# marbles_v70.net
KiCad netlist of a schematic drawn in EAGLE
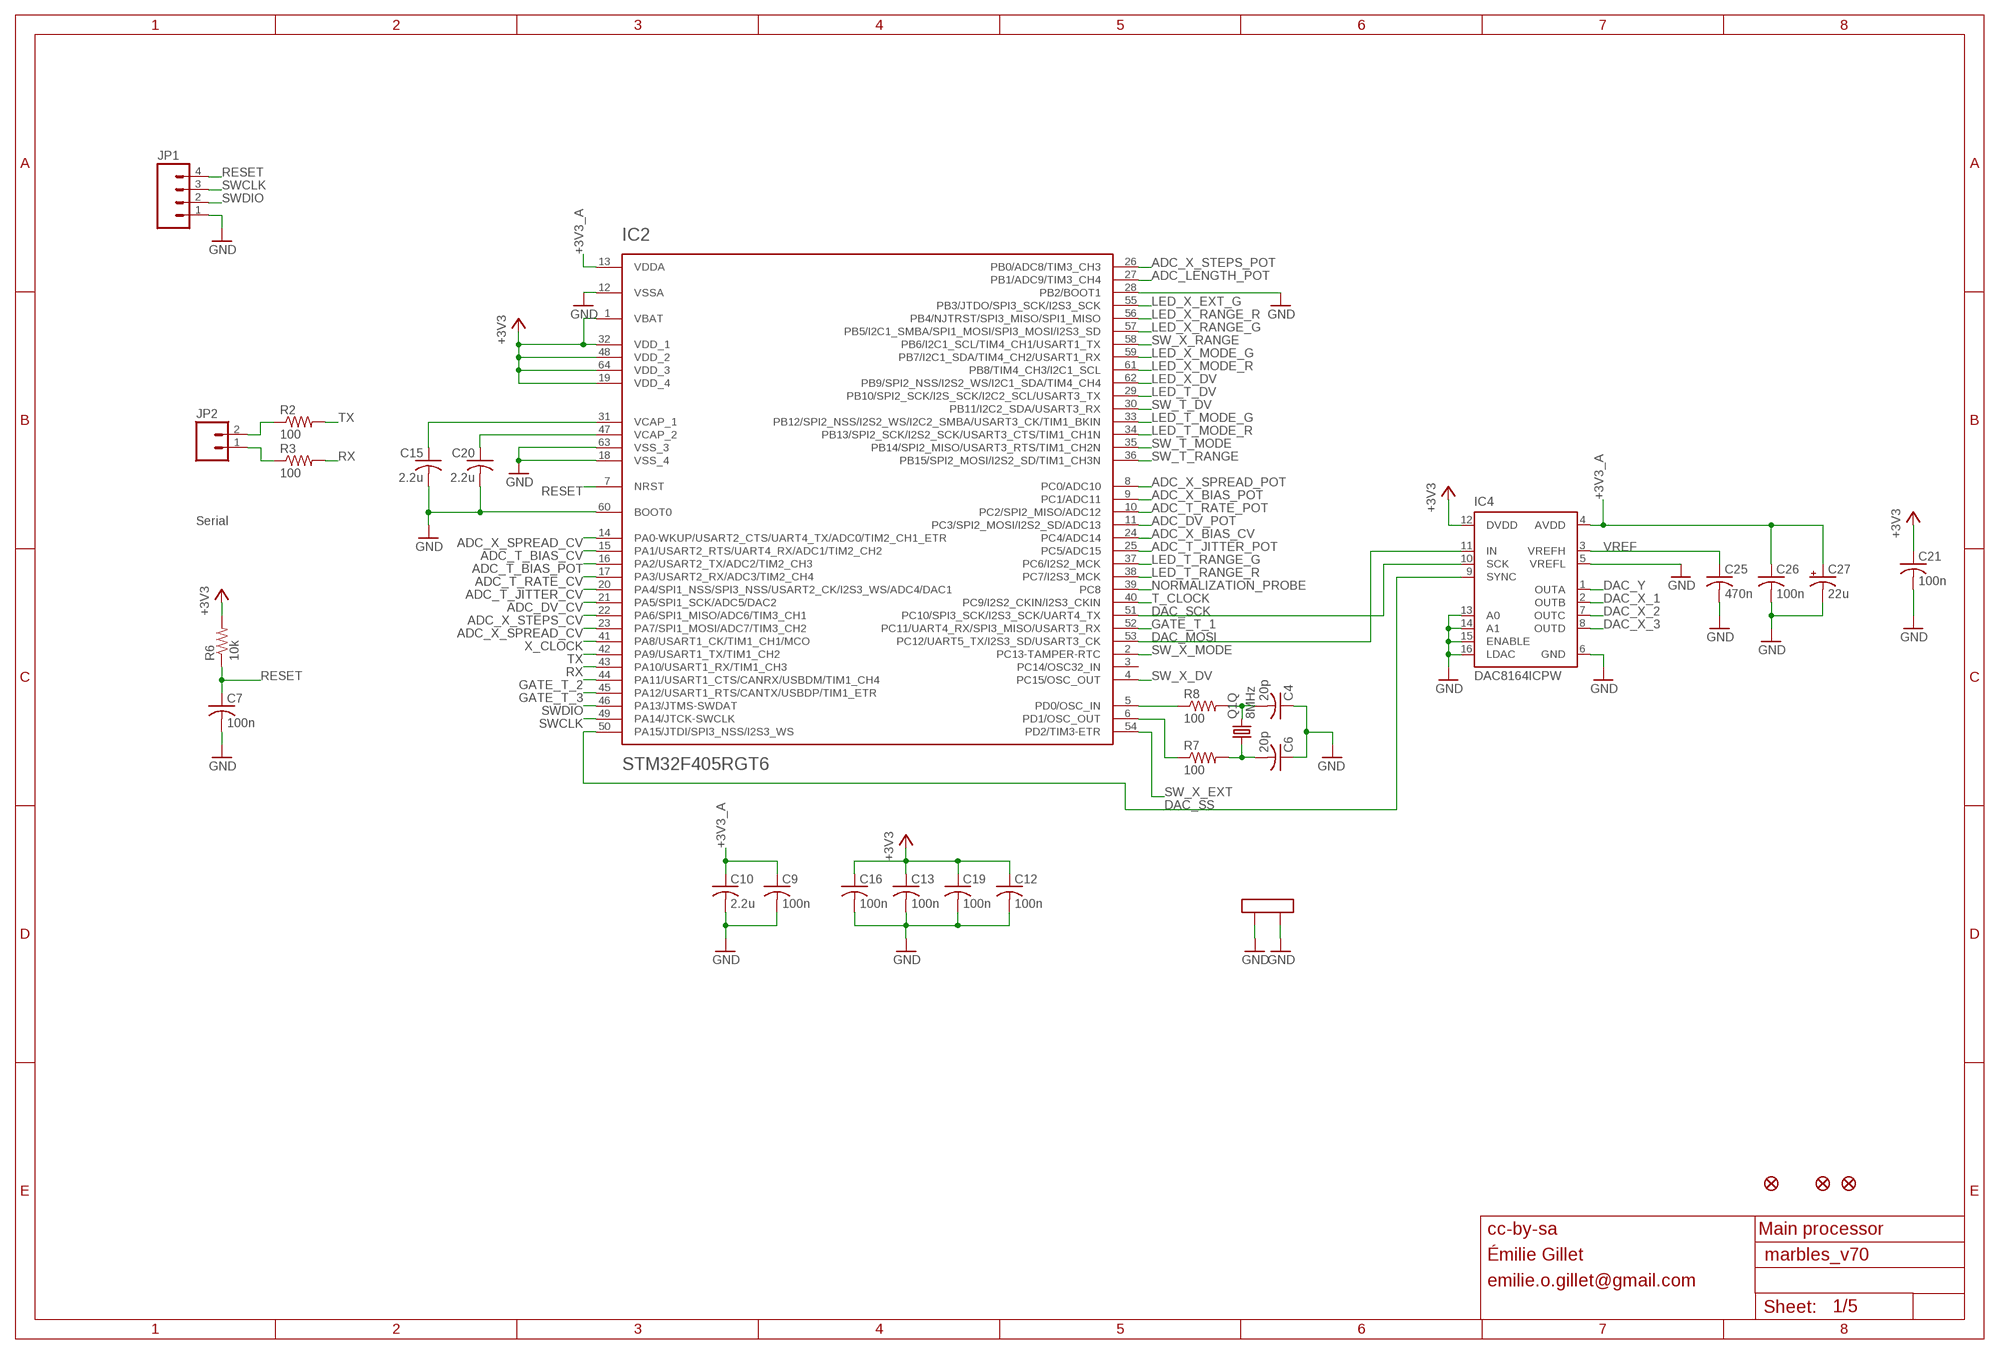
[diagram p0: schematic, sheet 1]
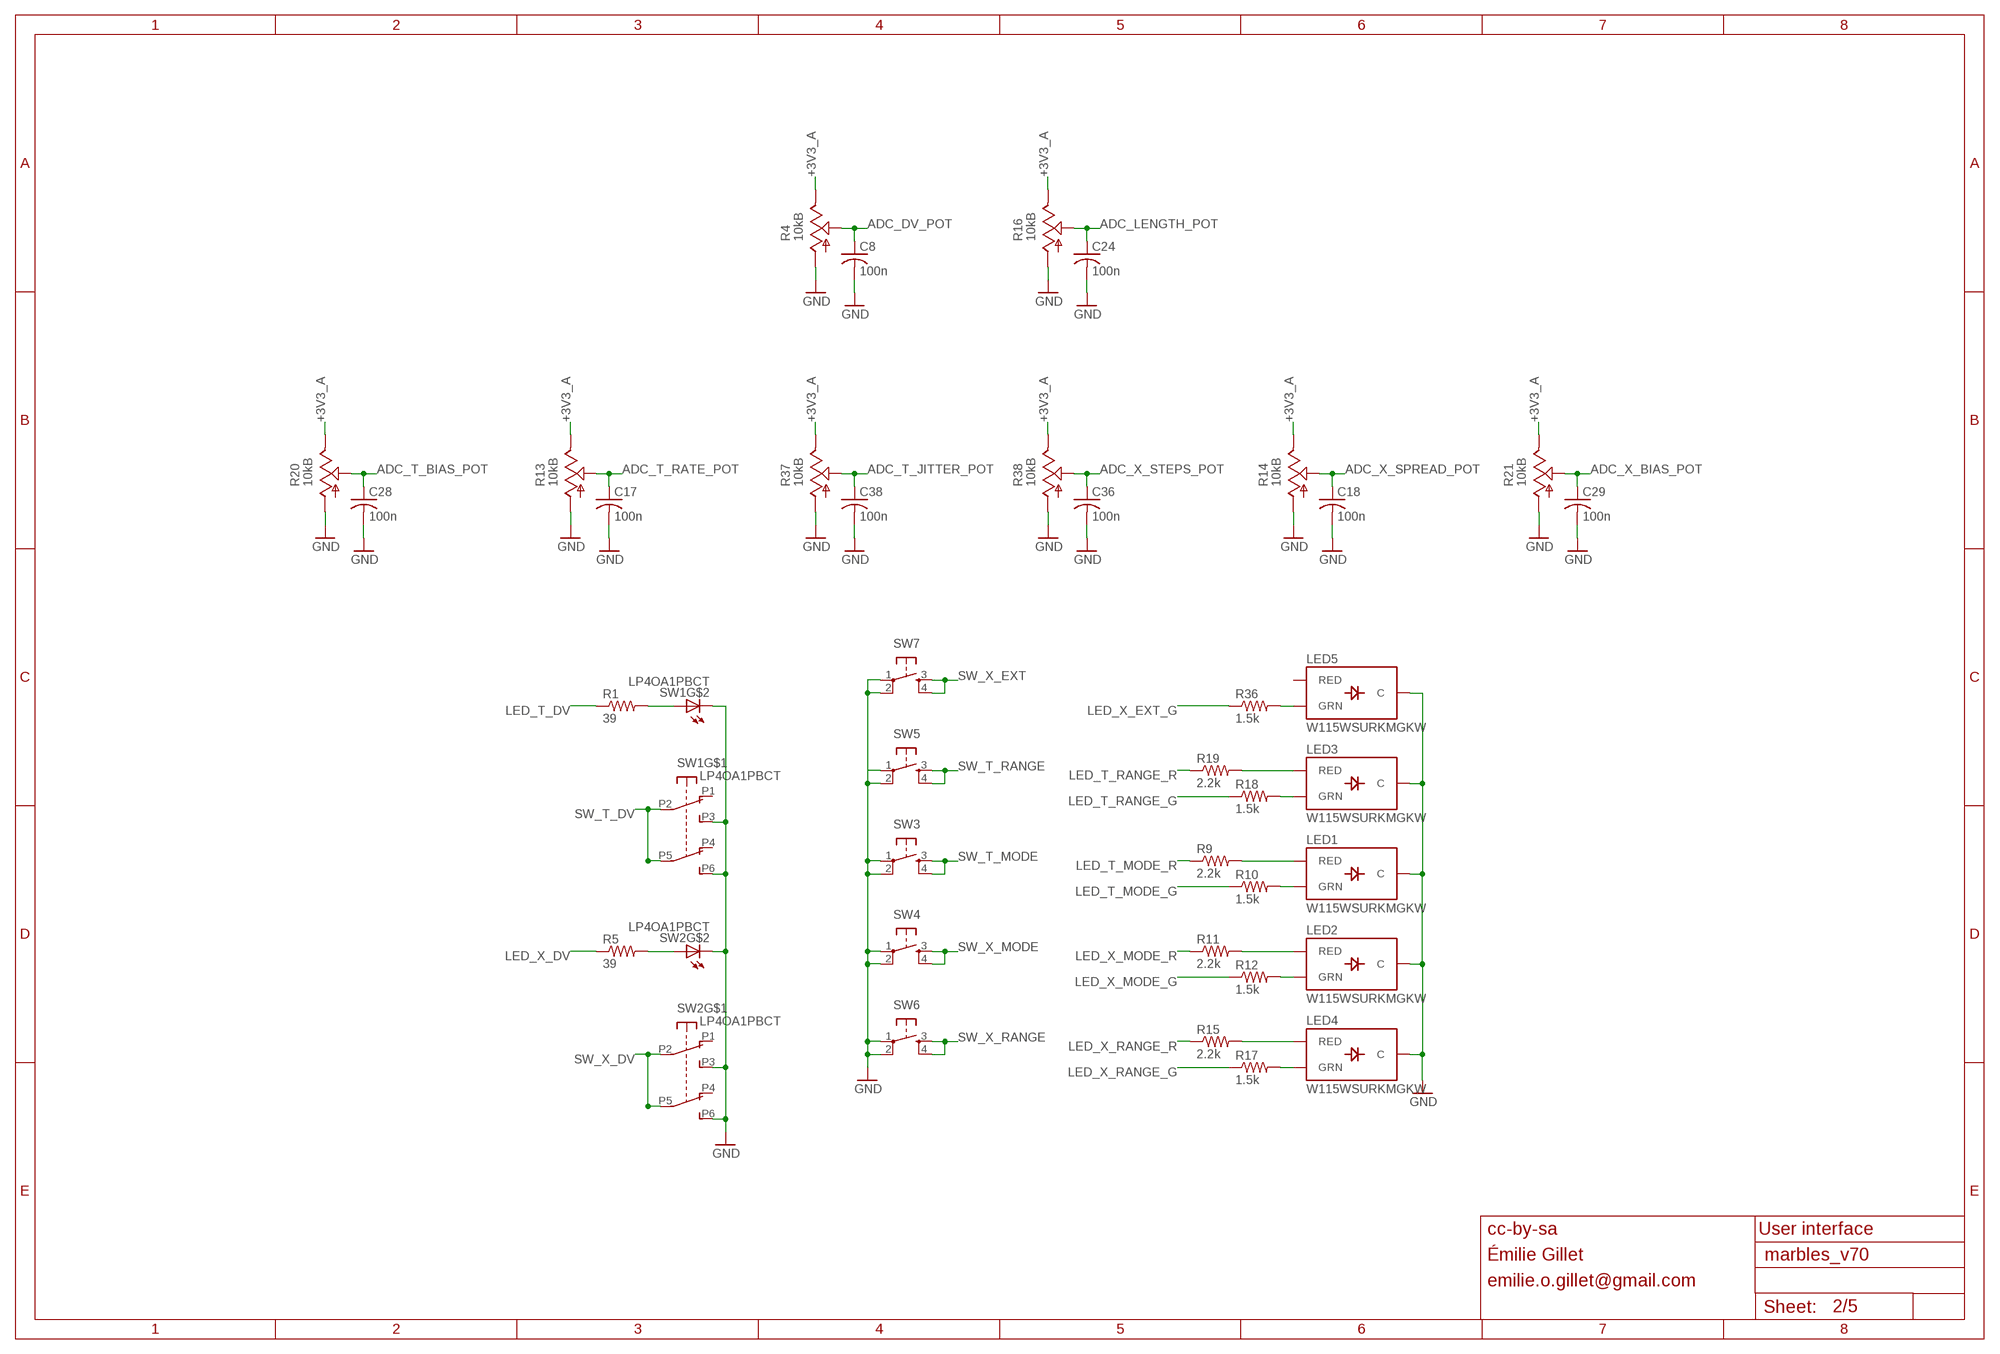
[diagram p1: schematic, sheet 2]
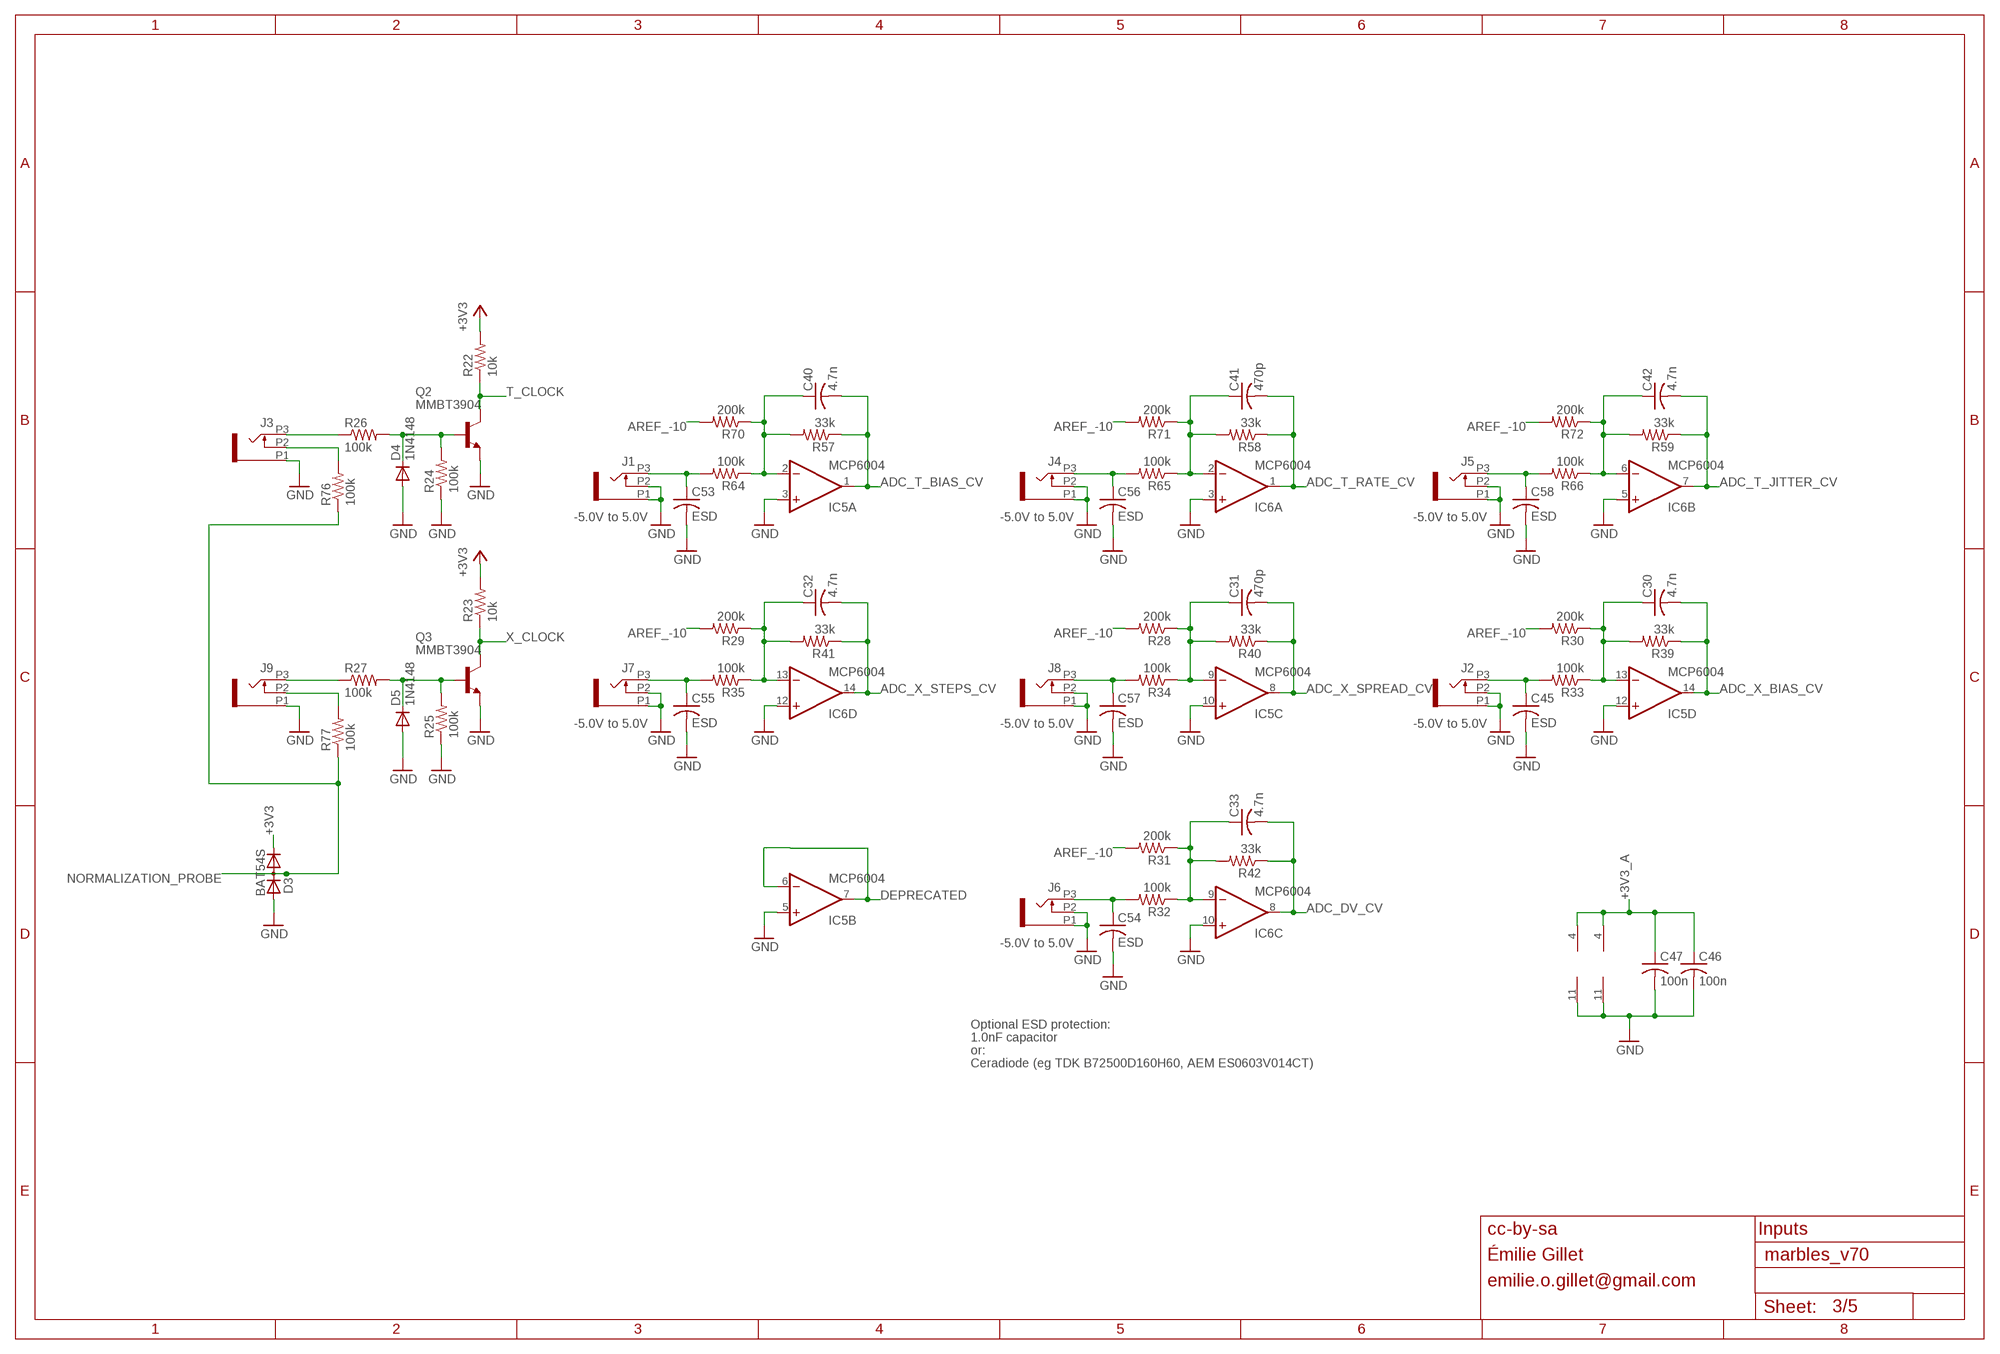
[diagram p2: schematic, sheet 3]
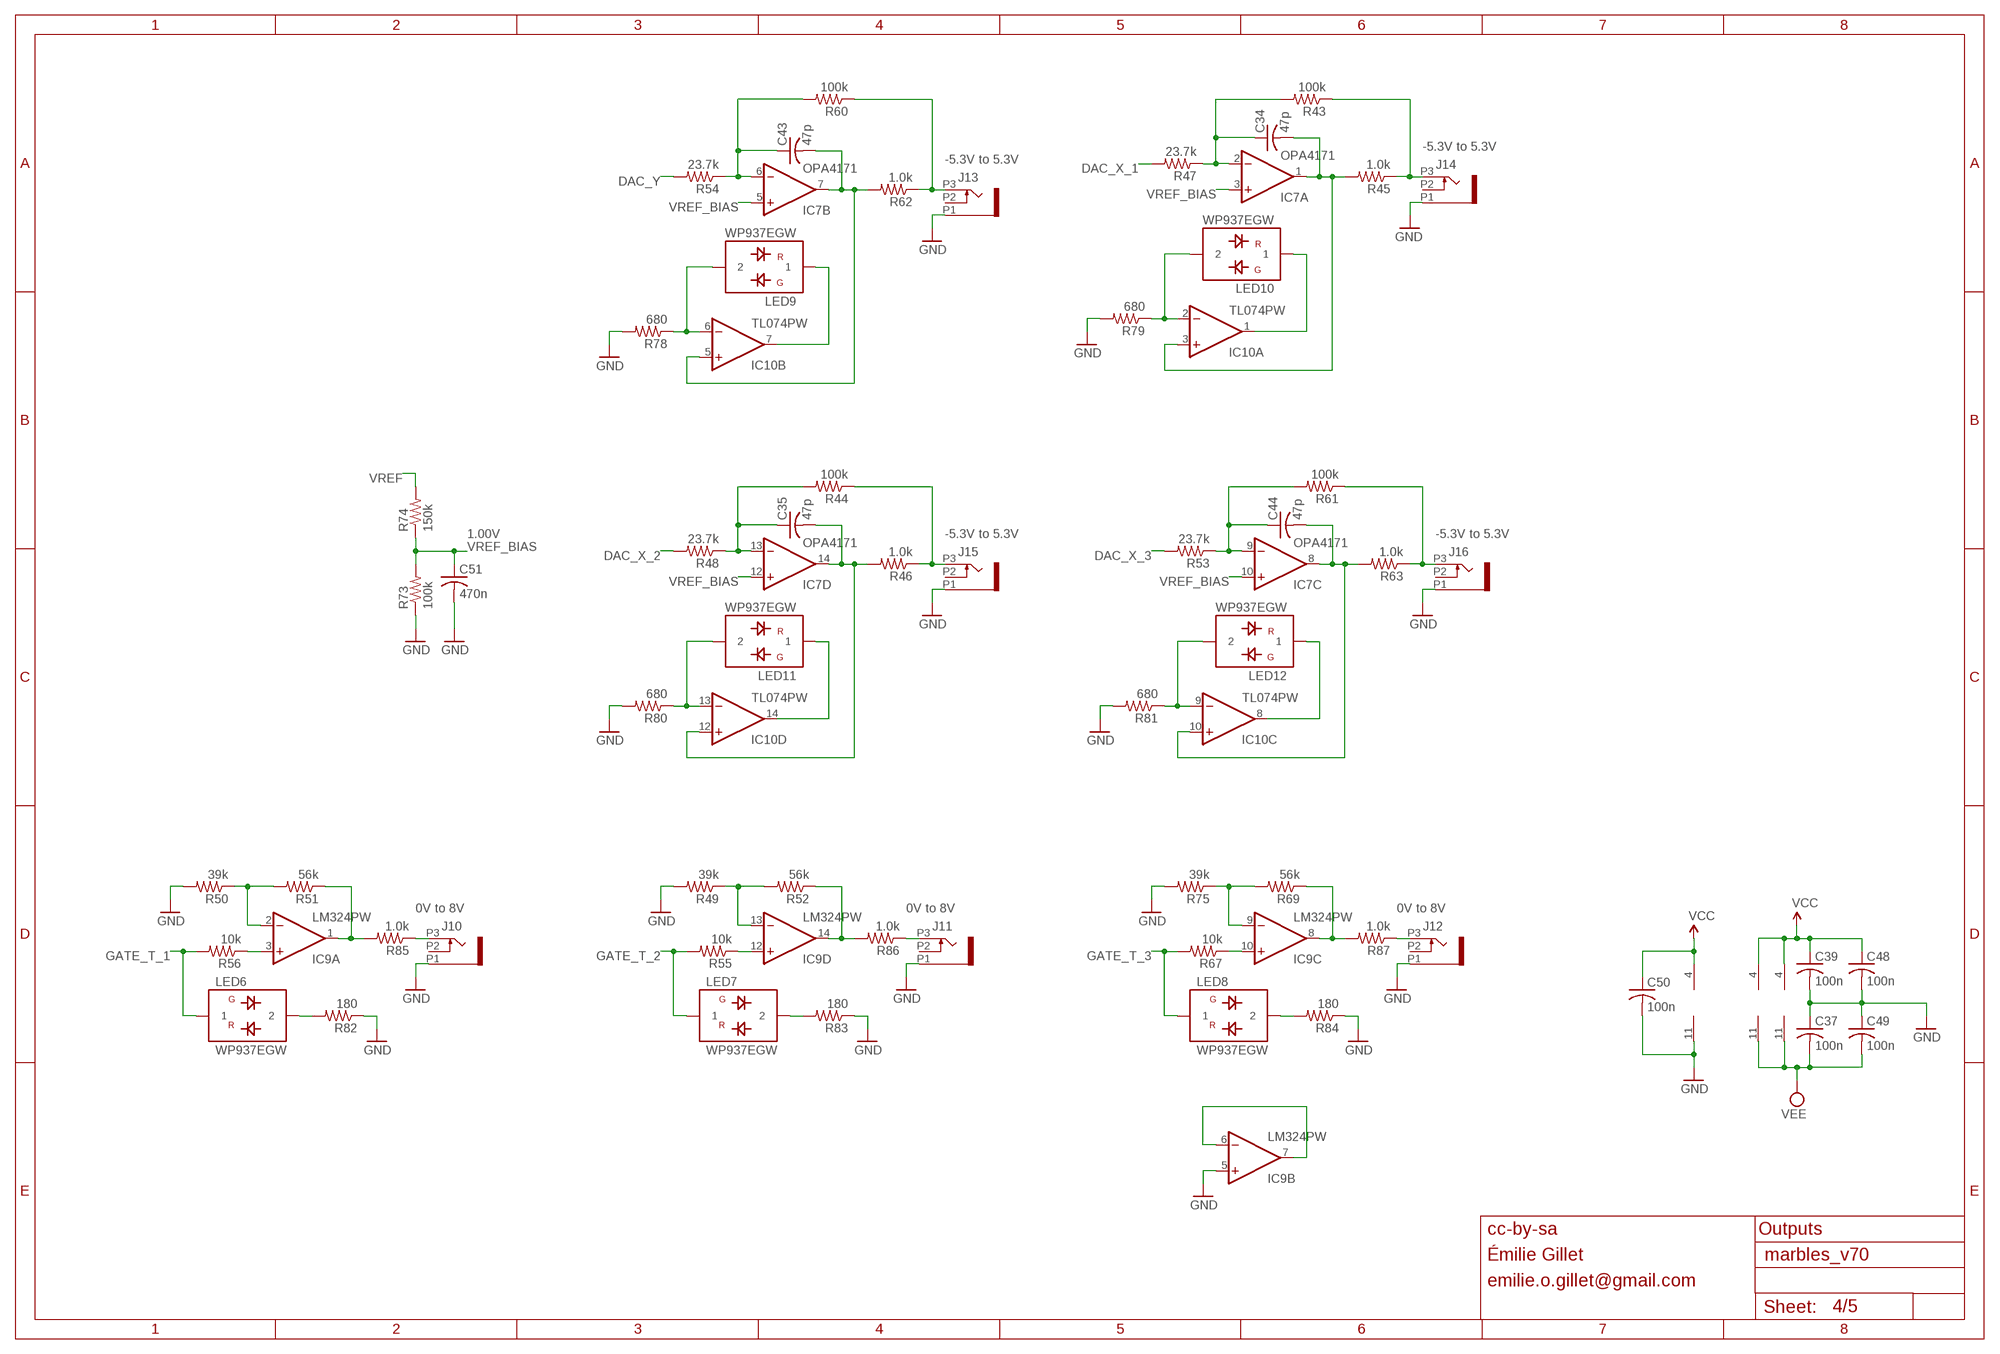
[diagram p3: schematic, sheet 4]
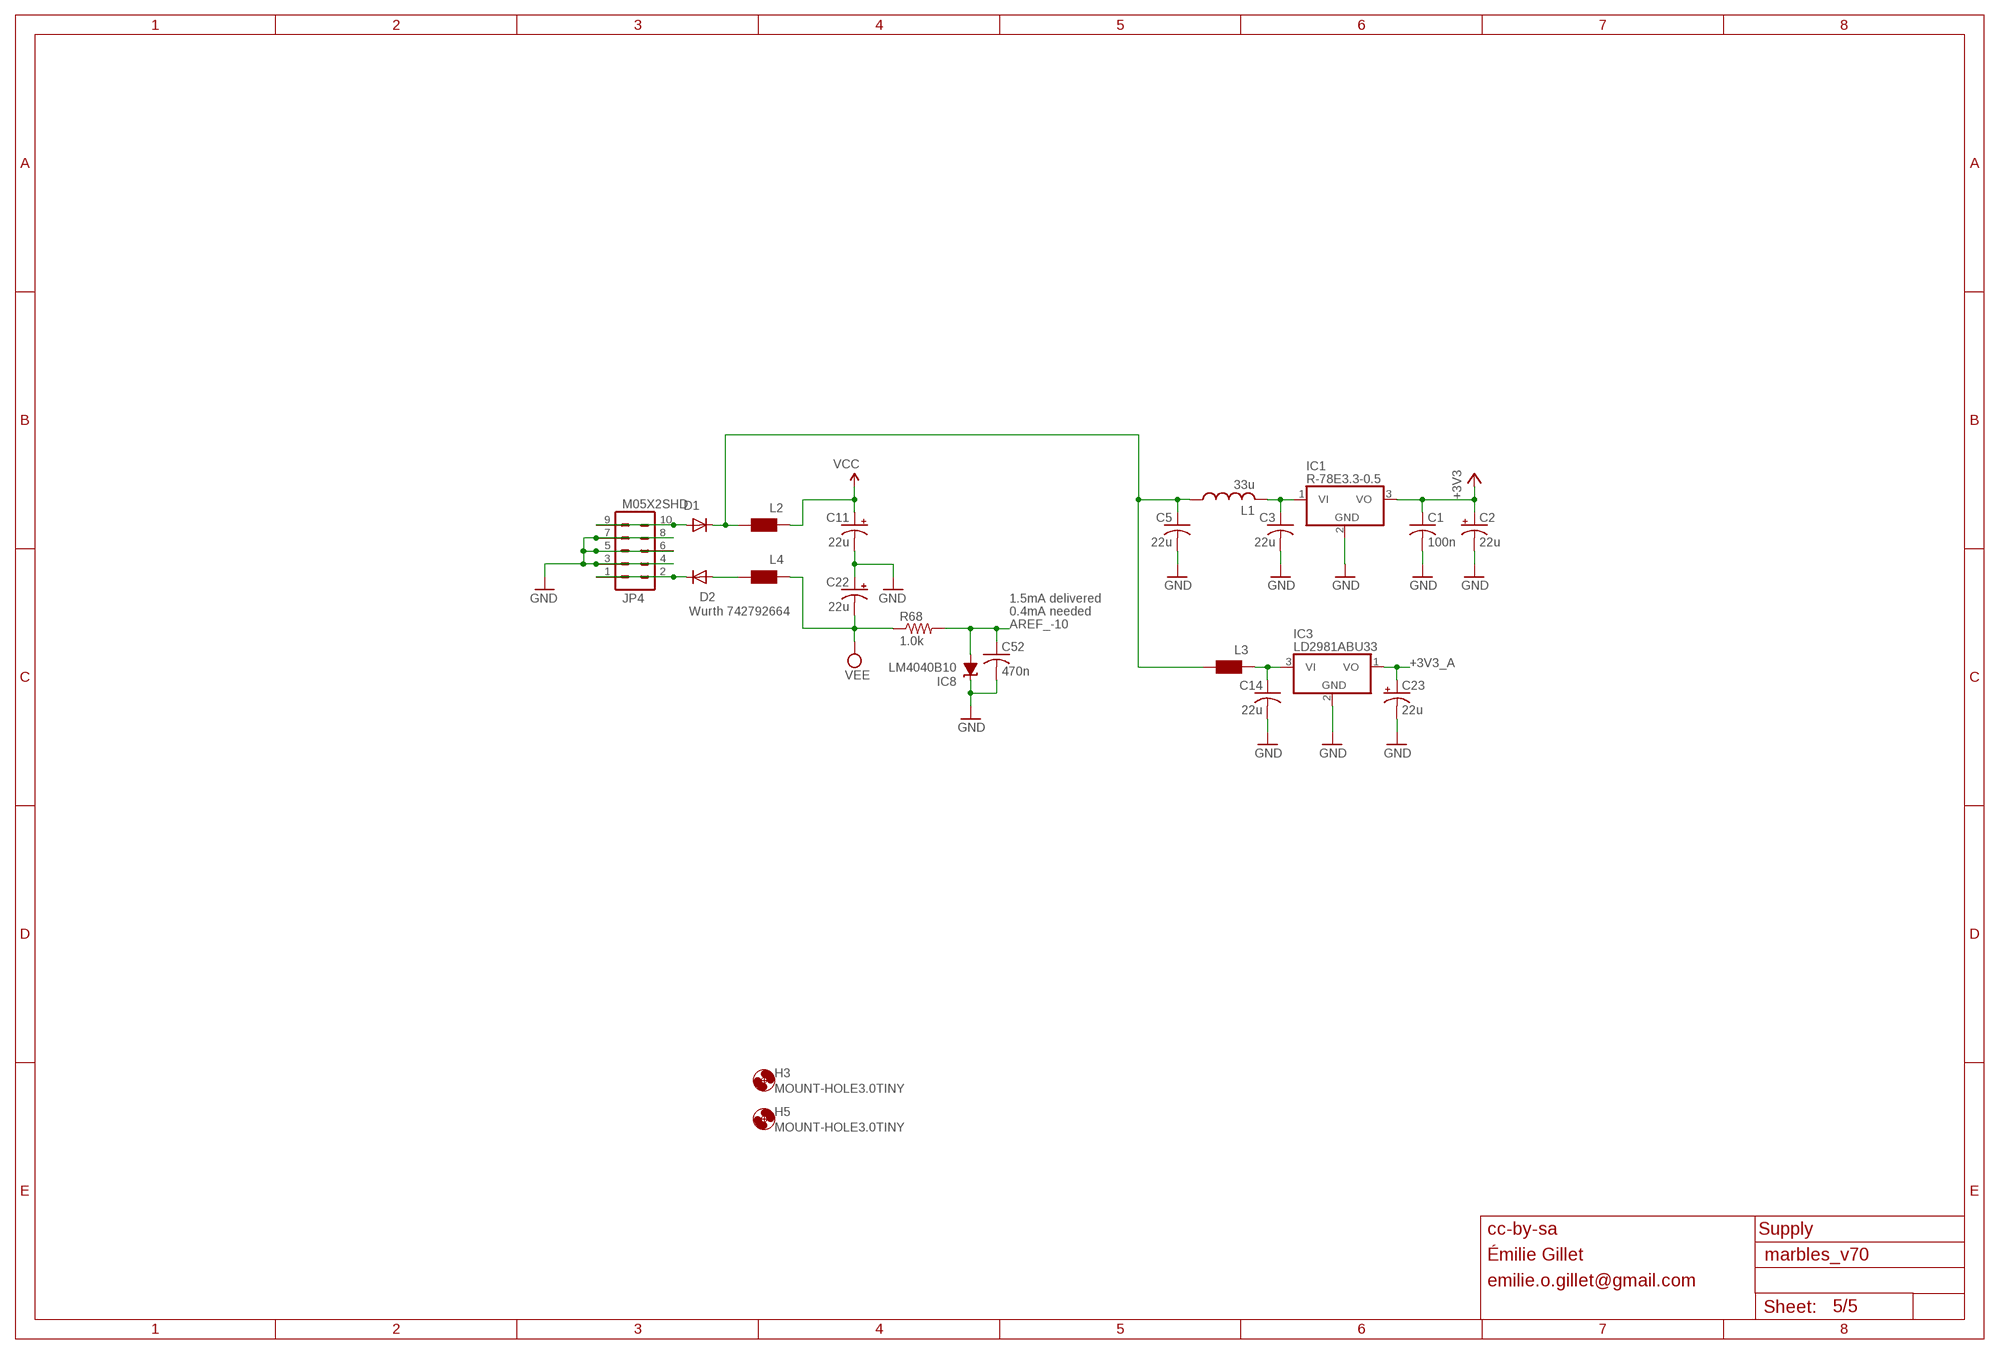
[diagram p4: schematic, sheet 5]

(export (version "E")
  (design (tool "Eeschema 10.0.6"))
  (components
    (comp (ref "C34")
      (value "47p")
      (footprint "eagle-import:C0402")
      (libsource (lib "eagle-import") (part "C-USC0402"))
    )
    (comp (ref "C35")
      (value "47p")
      (footprint "eagle-import:C0402")
      (libsource (lib "eagle-import") (part "C-USC0402"))
    )
    (comp (ref "C37")
      (value "100n")
      (footprint "eagle-import:C0402")
      (libsource (lib "eagle-import") (part "C-USC0402"))
    )
    (comp (ref "C39")
      (value "100n")
      (footprint "eagle-import:C0402")
      (libsource (lib "eagle-import") (part "C-USC0402"))
    )
    (comp (ref "C43")
      (value "47p")
      (footprint "eagle-import:C0402")
      (libsource (lib "eagle-import") (part "C-USC0402"))
    )
    (comp (ref "C44")
      (value "47p")
      (footprint "eagle-import:C0402")
      (libsource (lib "eagle-import") (part "C-USC0402"))
    )
    (comp (ref "C48")
      (value "100n")
      (footprint "eagle-import:C0402")
      (libsource (lib "eagle-import") (part "C-USC0402"))
    )
    (comp (ref "C49")
      (value "100n")
      (footprint "eagle-import:C0402")
      (libsource (lib "eagle-import") (part "C-USC0402"))
    )
    (comp (ref "C50")
      (value "100n")
      (footprint "eagle-import:C0402")
      (libsource (lib "eagle-import") (part "C-USC0402"))
    )
    (comp (ref "C51")
      (value "470n")
      (footprint "eagle-import:C0402")
      (libsource (lib "eagle-import") (part "C-USC0402"))
    )
    (comp (ref "IC7")
      (value "OPA4171")
      (footprint "eagle-import:TSSOP14_065")
      (libsource (lib "eagle-import") (part "TL074PW"))
    )
    (comp (ref "IC9")
      (value "LM324PW")
      (footprint "eagle-import:TSSOP14_065")
      (libsource (lib "eagle-import") (part "TL074PW"))
    )
    (comp (ref "IC10")
      (value "TL074PW")
      (footprint "eagle-import:TSSOP14_065")
      (libsource (lib "eagle-import") (part "TL074PW"))
    )
    (comp (ref "J10")
      (value "PJ301_THONKICONN6")
      (footprint "eagle-import:WQP_PJ_301M6")
      (libsource (lib "eagle-import") (part "PJ301_THONKICONN6"))
    )
    (comp (ref "J11")
      (value "PJ301_THONKICONN6")
      (footprint "eagle-import:WQP_PJ_301M6")
      (libsource (lib "eagle-import") (part "PJ301_THONKICONN6"))
    )
    (comp (ref "J12")
      (value "PJ301_THONKICONN6")
      (footprint "eagle-import:WQP_PJ_301M6")
      (libsource (lib "eagle-import") (part "PJ301_THONKICONN6"))
    )
    (comp (ref "J13")
      (value "PJ301_THONKICONN6")
      (footprint "eagle-import:WQP_PJ_301M6")
      (libsource (lib "eagle-import") (part "PJ301_THONKICONN6"))
    )
    (comp (ref "J14")
      (value "PJ301_THONKICONN6")
      (footprint "eagle-import:WQP_PJ_301M6")
      (libsource (lib "eagle-import") (part "PJ301_THONKICONN6"))
    )
    (comp (ref "J15")
      (value "PJ301_THONKICONN6")
      (footprint "eagle-import:WQP_PJ_301M6")
      (libsource (lib "eagle-import") (part "PJ301_THONKICONN6"))
    )
    (comp (ref "J16")
      (value "PJ301_THONKICONN6")
      (footprint "eagle-import:WQP_PJ_301M6")
      (libsource (lib "eagle-import") (part "PJ301_THONKICONN6"))
    )
    (comp (ref "LED6")
      (value "WP937EGW")
      (footprint "eagle-import:LED3MM")
      (libsource (lib "eagle-import") (part "LED-BICOLOR-SHARED-THROUGHHOLE"))
    )
    (comp (ref "LED7")
      (value "WP937EGW")
      (footprint "eagle-import:LED3MM")
      (libsource (lib "eagle-import") (part "LED-BICOLOR-SHARED-THROUGHHOLE"))
    )
    (comp (ref "LED8")
      (value "WP937EGW")
      (footprint "eagle-import:LED3MM")
      (libsource (lib "eagle-import") (part "LED-BICOLOR-SHARED-THROUGHHOLE"))
    )
    (comp (ref "LED9")
      (value "WP937EGW")
      (footprint "eagle-import:LED3MM")
      (libsource (lib "eagle-import") (part "LED-BICOLOR-SHARED-THROUGHHOLE"))
    )
    (comp (ref "LED10")
      (value "WP937EGW")
      (footprint "eagle-import:LED3MM")
      (libsource (lib "eagle-import") (part "LED-BICOLOR-SHARED-THROUGHHOLE"))
    )
    (comp (ref "LED11")
      (value "WP937EGW")
      (footprint "eagle-import:LED3MM")
      (libsource (lib "eagle-import") (part "LED-BICOLOR-SHARED-THROUGHHOLE"))
    )
    (comp (ref "LED12")
      (value "WP937EGW")
      (footprint "eagle-import:LED3MM")
      (libsource (lib "eagle-import") (part "LED-BICOLOR-SHARED-THROUGHHOLE"))
    )
    (comp (ref "R43")
      (value "100k")
      (footprint "eagle-import:R0402")
      (libsource (lib "eagle-import") (part "R-US_R0402"))
    )
    (comp (ref "R44")
      (value "100k")
      (footprint "eagle-import:R0402")
      (libsource (lib "eagle-import") (part "R-US_R0402"))
    )
    (comp (ref "R45")
      (value "1.0k")
      (footprint "eagle-import:R0603")
      (libsource (lib "eagle-import") (part "R-US_R0603"))
    )
    (comp (ref "R46")
      (value "1.0k")
      (footprint "eagle-import:R0603")
      (libsource (lib "eagle-import") (part "R-US_R0603"))
    )
    (comp (ref "R47")
      (value "23.7k")
      (footprint "eagle-import:R0402")
      (libsource (lib "eagle-import") (part "R-US_R0402"))
    )
    (comp (ref "R48")
      (value "23.7k")
      (footprint "eagle-import:R0402")
      (libsource (lib "eagle-import") (part "R-US_R0402"))
    )
    (comp (ref "R49")
      (value "39k")
      (footprint "eagle-import:R0402")
      (libsource (lib "eagle-import") (part "R-US_R0402"))
    )
    (comp (ref "R50")
      (value "39k")
      (footprint "eagle-import:R0402")
      (libsource (lib "eagle-import") (part "R-US_R0402"))
    )
    (comp (ref "R51")
      (value "56k")
      (footprint "eagle-import:R0402")
      (libsource (lib "eagle-import") (part "R-US_R0402"))
    )
    (comp (ref "R52")
      (value "56k")
      (footprint "eagle-import:R0402")
      (libsource (lib "eagle-import") (part "R-US_R0402"))
    )
    (comp (ref "R53")
      (value "23.7k")
      (footprint "eagle-import:R0402")
      (libsource (lib "eagle-import") (part "R-US_R0402"))
    )
    (comp (ref "R54")
      (value "23.7k")
      (footprint "eagle-import:R0402")
      (libsource (lib "eagle-import") (part "R-US_R0402"))
    )
    (comp (ref "R55")
      (value "10k")
      (footprint "eagle-import:R0402")
      (libsource (lib "eagle-import") (part "R-US_R0402"))
    )
    (comp (ref "R56")
      (value "10k")
      (footprint "eagle-import:R0402")
      (libsource (lib "eagle-import") (part "R-US_R0402"))
    )
    (comp (ref "R60")
      (value "100k")
      (footprint "eagle-import:R0402")
      (libsource (lib "eagle-import") (part "R-US_R0402"))
    )
    (comp (ref "R61")
      (value "100k")
      (footprint "eagle-import:R0402")
      (libsource (lib "eagle-import") (part "R-US_R0402"))
    )
    (comp (ref "R62")
      (value "1.0k")
      (footprint "eagle-import:R0603")
      (libsource (lib "eagle-import") (part "R-US_R0603"))
    )
    (comp (ref "R63")
      (value "1.0k")
      (footprint "eagle-import:R0603")
      (libsource (lib "eagle-import") (part "R-US_R0603"))
    )
    (comp (ref "R67")
      (value "10k")
      (footprint "eagle-import:R0402")
      (libsource (lib "eagle-import") (part "R-US_R0402"))
    )
    (comp (ref "R69")
      (value "56k")
      (footprint "eagle-import:R0402")
      (libsource (lib "eagle-import") (part "R-US_R0402"))
    )
    (comp (ref "R73")
      (value "100k")
      (footprint "eagle-import:R0402")
      (libsource (lib "eagle-import") (part "R-US_R0402"))
    )
    (comp (ref "R74")
      (value "150k")
      (footprint "eagle-import:R0402")
      (libsource (lib "eagle-import") (part "R-US_R0402"))
    )
    (comp (ref "R75")
      (value "39k")
      (footprint "eagle-import:R0402")
      (libsource (lib "eagle-import") (part "R-US_R0402"))
    )
    (comp (ref "R78")
      (value "680")
      (footprint "eagle-import:R0402")
      (libsource (lib "eagle-import") (part "R-US_R0402"))
    )
    (comp (ref "R79")
      (value "680")
      (footprint "eagle-import:R0402")
      (libsource (lib "eagle-import") (part "R-US_R0402"))
    )
    (comp (ref "R80")
      (value "680")
      (footprint "eagle-import:R0402")
      (libsource (lib "eagle-import") (part "R-US_R0402"))
    )
    (comp (ref "R81")
      (value "680")
      (footprint "eagle-import:R0402")
      (libsource (lib "eagle-import") (part "R-US_R0402"))
    )
    (comp (ref "R82")
      (value "180")
      (footprint "eagle-import:R0402")
      (libsource (lib "eagle-import") (part "R-US_R0402"))
    )
    (comp (ref "R83")
      (value "180")
      (footprint "eagle-import:R0402")
      (libsource (lib "eagle-import") (part "R-US_R0402"))
    )
    (comp (ref "R84")
      (value "180")
      (footprint "eagle-import:R0402")
      (libsource (lib "eagle-import") (part "R-US_R0402"))
    )
    (comp (ref "R85")
      (value "1.0k")
      (footprint "eagle-import:R0603")
      (libsource (lib "eagle-import") (part "R-US_R0603"))
    )
    (comp (ref "R86")
      (value "1.0k")
      (footprint "eagle-import:R0603")
      (libsource (lib "eagle-import") (part "R-US_R0603"))
    )
    (comp (ref "R87")
      (value "1.0k")
      (footprint "eagle-import:R0603")
      (libsource (lib "eagle-import") (part "R-US_R0603"))
    )
    (comp (ref "C8")
      (value "100n")
      (footprint "eagle-import:C0402")
      (libsource (lib "eagle-import") (part "C-USC0402"))
    )
    (comp (ref "C17")
      (value "100n")
      (footprint "eagle-import:C0402")
      (libsource (lib "eagle-import") (part "C-USC0402"))
    )
    (comp (ref "C18")
      (value "100n")
      (footprint "eagle-import:C0402")
      (libsource (lib "eagle-import") (part "C-USC0402"))
    )
    (comp (ref "C24")
      (value "100n")
      (footprint "eagle-import:C0402")
      (libsource (lib "eagle-import") (part "C-USC0402"))
    )
    (comp (ref "C28")
      (value "100n")
      (footprint "eagle-import:C0402")
      (libsource (lib "eagle-import") (part "C-USC0402"))
    )
    (comp (ref "C29")
      (value "100n")
      (footprint "eagle-import:C0402")
      (libsource (lib "eagle-import") (part "C-USC0402"))
    )
    (comp (ref "C36")
      (value "100n")
      (footprint "eagle-import:C0402")
      (libsource (lib "eagle-import") (part "C-USC0402"))
    )
    (comp (ref "C38")
      (value "100n")
      (footprint "eagle-import:C0402")
      (libsource (lib "eagle-import") (part "C-USC0402"))
    )
    (comp (ref "LED1")
      (value "W115WSURKMGKW")
      (footprint "eagle-import:LED-BICOLOR-THROUGHHOLE-2.54")
      (libsource (lib "eagle-import") (part "LED-BICOLOR-THROUGHHOLE2.54"))
    )
    (comp (ref "LED2")
      (value "W115WSURKMGKW")
      (footprint "eagle-import:LED-BICOLOR-THROUGHHOLE-2.54")
      (libsource (lib "eagle-import") (part "LED-BICOLOR-THROUGHHOLE2.54"))
    )
    (comp (ref "LED3")
      (value "W115WSURKMGKW")
      (footprint "eagle-import:LED-BICOLOR-THROUGHHOLE-2.54")
      (libsource (lib "eagle-import") (part "LED-BICOLOR-THROUGHHOLE2.54"))
    )
    (comp (ref "LED4")
      (value "W115WSURKMGKW")
      (footprint "eagle-import:LED-BICOLOR-THROUGHHOLE-2.54")
      (libsource (lib "eagle-import") (part "LED-BICOLOR-THROUGHHOLE2.54"))
    )
    (comp (ref "LED5")
      (value "W115WSURKMGKW")
      (footprint "eagle-import:LED-BICOLOR-THROUGHHOLE-2.54")
      (libsource (lib "eagle-import") (part "LED-BICOLOR-THROUGHHOLE2.54"))
    )
    (comp (ref "R1")
      (value "39")
      (footprint "eagle-import:R0402")
      (libsource (lib "eagle-import") (part "R-US_R0402"))
    )
    (comp (ref "R4")
      (value "10kB")
      (footprint "eagle-import:ALPS_POT_VERTICAL_PS")
      (libsource (lib "eagle-import") (part "POT_USVERTICAL_PS"))
    )
    (comp (ref "R5")
      (value "39")
      (footprint "eagle-import:R0402")
      (libsource (lib "eagle-import") (part "R-US_R0402"))
    )
    (comp (ref "R9")
      (value "2.2k")
      (footprint "eagle-import:R0402")
      (libsource (lib "eagle-import") (part "R-US_R0402"))
    )
    (comp (ref "R10")
      (value "1.5k")
      (footprint "eagle-import:R0402")
      (libsource (lib "eagle-import") (part "R-US_R0402"))
    )
    (comp (ref "R11")
      (value "2.2k")
      (footprint "eagle-import:R0402")
      (libsource (lib "eagle-import") (part "R-US_R0402"))
    )
    (comp (ref "R12")
      (value "1.5k")
      (footprint "eagle-import:R0402")
      (libsource (lib "eagle-import") (part "R-US_R0402"))
    )
    (comp (ref "R13")
      (value "10kB")
      (footprint "eagle-import:ALPS_POT_VERTICAL_PS")
      (libsource (lib "eagle-import") (part "POT_USVERTICAL_PS"))
    )
    (comp (ref "R14")
      (value "10kB")
      (footprint "eagle-import:ALPS_POT_VERTICAL_PS")
      (libsource (lib "eagle-import") (part "POT_USVERTICAL_PS"))
    )
    (comp (ref "R15")
      (value "2.2k")
      (footprint "eagle-import:R0402")
      (libsource (lib "eagle-import") (part "R-US_R0402"))
    )
    (comp (ref "R16")
      (value "10kB")
      (footprint "eagle-import:ALPS_POT_VERTICAL_PS")
      (libsource (lib "eagle-import") (part "POT_USVERTICAL_PS"))
    )
    (comp (ref "R17")
      (value "1.5k")
      (footprint "eagle-import:R0402")
      (libsource (lib "eagle-import") (part "R-US_R0402"))
    )
    (comp (ref "R18")
      (value "1.5k")
      (footprint "eagle-import:R0402")
      (libsource (lib "eagle-import") (part "R-US_R0402"))
    )
    (comp (ref "R19")
      (value "2.2k")
      (footprint "eagle-import:R0402")
      (libsource (lib "eagle-import") (part "R-US_R0402"))
    )
    (comp (ref "R20")
      (value "10kB")
      (footprint "eagle-import:ALPS_POT_VERTICAL_PS")
      (libsource (lib "eagle-import") (part "POT_USVERTICAL_PS"))
    )
    (comp (ref "R21")
      (value "10kB")
      (footprint "eagle-import:ALPS_POT_VERTICAL_PS")
      (libsource (lib "eagle-import") (part "POT_USVERTICAL_PS"))
    )
    (comp (ref "R36")
      (value "1.5k")
      (footprint "eagle-import:R0402")
      (libsource (lib "eagle-import") (part "R-US_R0402"))
    )
    (comp (ref "R37")
      (value "10kB")
      (footprint "eagle-import:ALPS_POT_VERTICAL_PS")
      (libsource (lib "eagle-import") (part "POT_USVERTICAL_PS"))
    )
    (comp (ref "R38")
      (value "10kB")
      (footprint "eagle-import:ALPS_POT_VERTICAL_PS")
      (libsource (lib "eagle-import") (part "POT_USVERTICAL_PS"))
    )
    (comp (ref "SW1")
      (value "LP4OA1PBCT")
      (footprint "eagle-import:LP4OA1PBCT")
      (libsource (lib "eagle-import") (part "LP4OA1PBCT"))
    )
    (comp (ref "SW2")
      (value "LP4OA1PBCT")
      (footprint "eagle-import:LP4OA1PBCT")
      (libsource (lib "eagle-import") (part "LP4OA1PBCT"))
    )
    (comp (ref "SW3")
      (value "TAC_SWITCHPTH")
      (footprint "eagle-import:TACTILE-PTH")
      (libsource (lib "eagle-import") (part "TAC_SWITCHPTH"))
    )
    (comp (ref "SW4")
      (value "TAC_SWITCHPTH")
      (footprint "eagle-import:TACTILE-PTH")
      (libsource (lib "eagle-import") (part "TAC_SWITCHPTH"))
    )
    (comp (ref "SW5")
      (value "TAC_SWITCHPTH")
      (footprint "eagle-import:TACTILE-PTH")
      (libsource (lib "eagle-import") (part "TAC_SWITCHPTH"))
    )
    (comp (ref "SW6")
      (value "TAC_SWITCHPTH")
      (footprint "eagle-import:TACTILE-PTH")
      (libsource (lib "eagle-import") (part "TAC_SWITCHPTH"))
    )
    (comp (ref "SW7")
      (value "TAC_SWITCHPTH")
      (footprint "eagle-import:TACTILE-PTH")
      (libsource (lib "eagle-import") (part "TAC_SWITCHPTH"))
    )
    (comp (ref "C4")
      (value "20p")
      (footprint "eagle-import:C0402")
      (libsource (lib "eagle-import") (part "C-USC0402"))
    )
    (comp (ref "C6")
      (value "20p")
      (footprint "eagle-import:C0402")
      (libsource (lib "eagle-import") (part "C-USC0402"))
    )
    (comp (ref "C7")
      (value "100n")
      (footprint "eagle-import:C0402")
      (libsource (lib "eagle-import") (part "C-USC0402"))
    )
    (comp (ref "C9")
      (value "100n")
      (footprint "eagle-import:C0402")
      (libsource (lib "eagle-import") (part "C-USC0402"))
    )
    (comp (ref "C10")
      (value "2.2u")
      (footprint "eagle-import:C0805")
      (libsource (lib "eagle-import") (part "C-USC0805"))
    )
    (comp (ref "C12")
      (value "100n")
      (footprint "eagle-import:C0402")
      (libsource (lib "eagle-import") (part "C-USC0402"))
    )
    (comp (ref "C13")
      (value "100n")
      (footprint "eagle-import:C0402")
      (libsource (lib "eagle-import") (part "C-USC0402"))
    )
    (comp (ref "C15")
      (value "2.2u")
      (footprint "eagle-import:C0805")
      (libsource (lib "eagle-import") (part "C-USC0805"))
    )
    (comp (ref "C16")
      (value "100n")
      (footprint "eagle-import:C0402")
      (libsource (lib "eagle-import") (part "C-USC0402"))
    )
    (comp (ref "C19")
      (value "100n")
      (footprint "eagle-import:C0402")
      (libsource (lib "eagle-import") (part "C-USC0402"))
    )
    (comp (ref "C20")
      (value "2.2u")
      (footprint "eagle-import:C0805")
      (libsource (lib "eagle-import") (part "C-USC0805"))
    )
    (comp (ref "C21")
      (value "100n")
      (footprint "eagle-import:C0402")
      (libsource (lib "eagle-import") (part "C-USC0402"))
    )
    (comp (ref "C25")
      (value "470n")
      (footprint "eagle-import:C0402")
      (libsource (lib "eagle-import") (part "C-USC0402"))
    )
    (comp (ref "C26")
      (value "100n")
      (footprint "eagle-import:C0402")
      (libsource (lib "eagle-import") (part "C-USC0402"))
    )
    (comp (ref "C27")
      (value "22u")
      (footprint "eagle-import:PANASONIC_C")
      (libsource (lib "eagle-import") (part "CPOL-USC"))
    )
    (comp (ref "F1")
      (value "FIDUCIAL1X2")
      (footprint "eagle-import:FIDUCIAL-1X2")
      (libsource (lib "eagle-import") (part "FIDUCIAL1X2"))
    )
    (comp (ref "F2")
      (value "FIDUCIAL1X2")
      (footprint "eagle-import:FIDUCIAL-1X2")
      (libsource (lib "eagle-import") (part "FIDUCIAL1X2"))
    )
    (comp (ref "F3")
      (value "FIDUCIAL1X2")
      (footprint "eagle-import:FIDUCIAL-1X2")
      (libsource (lib "eagle-import") (part "FIDUCIAL1X2"))
    )
    (comp (ref "IC2")
      (value "STM32F405RGT6")
      (footprint "eagle-import:TQFP-10X10-64")
      (libsource (lib "eagle-import") (part "STM32F20X"))
    )
    (comp (ref "IC4")
      (value "DAC8164ICPW")
      (footprint "eagle-import:SOP65P640X110-16N")
      (libsource (lib "eagle-import") (part "DAC8564"))
    )
    (comp (ref "JP1")
      (value "M04PTH")
      (footprint "eagle-import:1X04")
      (libsource (lib "eagle-import") (part "M04PTH"))
    )
    (comp (ref "JP2")
      (value "M02PTH")
      (footprint "eagle-import:1X02")
      (libsource (lib "eagle-import") (part "M02PTH"))
    )
    (comp (ref "Q1")
      (value "8MHz")
      (footprint "eagle-import:CTS406")
      (libsource (lib "eagle-import") (part "CRYSTAL"))
    )
    (comp (ref "R2")
      (value "100")
      (footprint "eagle-import:R0402")
      (libsource (lib "eagle-import") (part "R-US_R0402"))
    )
    (comp (ref "R3")
      (value "100")
      (footprint "eagle-import:R0402")
      (libsource (lib "eagle-import") (part "R-US_R0402"))
    )
    (comp (ref "R6")
      (value "10k")
      (footprint "eagle-import:R0402")
      (libsource (lib "eagle-import") (part "R-US_R0402"))
    )
    (comp (ref "R7")
      (value "100")
      (footprint "eagle-import:R0402")
      (libsource (lib "eagle-import") (part "R-US_R0402"))
    )
    (comp (ref "R8")
      (value "100")
      (footprint "eagle-import:R0402")
      (libsource (lib "eagle-import") (part "R-US_R0402"))
    )
    (comp (ref "C30")
      (value "4.7n")
      (footprint "eagle-import:C0402")
      (libsource (lib "eagle-import") (part "C-USC0402"))
    )
    (comp (ref "C31")
      (value "470p")
      (footprint "eagle-import:C0402")
      (libsource (lib "eagle-import") (part "C-USC0402"))
    )
    (comp (ref "C32")
      (value "4.7n")
      (footprint "eagle-import:C0402")
      (libsource (lib "eagle-import") (part "C-USC0402"))
    )
    (comp (ref "C33")
      (value "4.7n")
      (footprint "eagle-import:C0402")
      (libsource (lib "eagle-import") (part "C-USC0402"))
    )
    (comp (ref "C40")
      (value "4.7n")
      (footprint "eagle-import:C0402")
      (libsource (lib "eagle-import") (part "C-USC0402"))
    )
    (comp (ref "C41")
      (value "470p")
      (footprint "eagle-import:C0402")
      (libsource (lib "eagle-import") (part "C-USC0402"))
    )
    (comp (ref "C42")
      (value "4.7n")
      (footprint "eagle-import:C0402")
      (libsource (lib "eagle-import") (part "C-USC0402"))
    )
    (comp (ref "C45")
      (value "ESD")
      (footprint "eagle-import:C0603")
      (libsource (lib "eagle-import") (part "C-USC0603"))
    )
    (comp (ref "C46")
      (value "100n")
      (footprint "eagle-import:C0402")
      (libsource (lib "eagle-import") (part "C-USC0402"))
    )
    (comp (ref "C47")
      (value "100n")
      (footprint "eagle-import:C0402")
      (libsource (lib "eagle-import") (part "C-USC0402"))
    )
    (comp (ref "C53")
      (value "ESD")
      (footprint "eagle-import:C0603")
      (libsource (lib "eagle-import") (part "C-USC0603"))
    )
    (comp (ref "C54")
      (value "ESD")
      (footprint "eagle-import:C0603")
      (libsource (lib "eagle-import") (part "C-USC0603"))
    )
    (comp (ref "C55")
      (value "ESD")
      (footprint "eagle-import:C0603")
      (libsource (lib "eagle-import") (part "C-USC0603"))
    )
    (comp (ref "C56")
      (value "ESD")
      (footprint "eagle-import:C0603")
      (libsource (lib "eagle-import") (part "C-USC0603"))
    )
    (comp (ref "C57")
      (value "ESD")
      (footprint "eagle-import:C0603")
      (libsource (lib "eagle-import") (part "C-USC0603"))
    )
    (comp (ref "C58")
      (value "ESD")
      (footprint "eagle-import:C0603")
      (libsource (lib "eagle-import") (part "C-USC0603"))
    )
    (comp (ref "D3")
      (value "BAT54S")
      (footprint "eagle-import:SOT23")
      (libsource (lib "eagle-import") (part "DIODE_2CACA-SOT23"))
    )
    (comp (ref "D4")
      (value "1N4148")
      (footprint "eagle-import:SOD523")
      (libsource (lib "eagle-import") (part "DIODE-SOD523"))
    )
    (comp (ref "D5")
      (value "1N4148")
      (footprint "eagle-import:SOD523")
      (libsource (lib "eagle-import") (part "DIODE-SOD523"))
    )
    (comp (ref "IC5")
      (value "MCP6004")
      (footprint "eagle-import:TSSOP14_065")
      (libsource (lib "eagle-import") (part "TL074PW"))
    )
    (comp (ref "IC6")
      (value "MCP6004")
      (footprint "eagle-import:TSSOP14_065")
      (libsource (lib "eagle-import") (part "TL074PW"))
    )
    (comp (ref "J1")
      (value "PJ301_THONKICONN6")
      (footprint "eagle-import:WQP_PJ_301M6")
      (libsource (lib "eagle-import") (part "PJ301_THONKICONN6"))
    )
    (comp (ref "J2")
      (value "PJ301_THONKICONN6")
      (footprint "eagle-import:WQP_PJ_301M6")
      (libsource (lib "eagle-import") (part "PJ301_THONKICONN6"))
    )
    (comp (ref "J3")
      (value "PJ301_THONKICONN6")
      (footprint "eagle-import:WQP_PJ_301M6")
      (libsource (lib "eagle-import") (part "PJ301_THONKICONN6"))
    )
    (comp (ref "J4")
      (value "PJ301_THONKICONN6")
      (footprint "eagle-import:WQP_PJ_301M6")
      (libsource (lib "eagle-import") (part "PJ301_THONKICONN6"))
    )
    (comp (ref "J5")
      (value "PJ301_THONKICONN6")
      (footprint "eagle-import:WQP_PJ_301M6")
      (libsource (lib "eagle-import") (part "PJ301_THONKICONN6"))
    )
    (comp (ref "J6")
      (value "PJ301_THONKICONN6")
      (footprint "eagle-import:WQP_PJ_301M6")
      (libsource (lib "eagle-import") (part "PJ301_THONKICONN6"))
    )
    (comp (ref "J7")
      (value "PJ301_THONKICONN6")
      (footprint "eagle-import:WQP_PJ_301M6")
      (libsource (lib "eagle-import") (part "PJ301_THONKICONN6"))
    )
    (comp (ref "J8")
      (value "PJ301_THONKICONN6")
      (footprint "eagle-import:WQP_PJ_301M6")
      (libsource (lib "eagle-import") (part "PJ301_THONKICONN6"))
    )
    (comp (ref "J9")
      (value "PJ301_THONKICONN6")
      (footprint "eagle-import:WQP_PJ_301M6")
      (libsource (lib "eagle-import") (part "PJ301_THONKICONN6"))
    )
    (comp (ref "Q2")
      (value "MMBT3904")
      (footprint "eagle-import:SOT23-BEC")
      (libsource (lib "eagle-import") (part "-NPN-SOT23-BECMMBT3904LT1"))
    )
    (comp (ref "Q3")
      (value "MMBT3904")
      (footprint "eagle-import:SOT23-BEC")
      (libsource (lib "eagle-import") (part "-NPN-SOT23-BECMMBT3904LT1"))
    )
    (comp (ref "R22")
      (value "10k")
      (footprint "eagle-import:R0402")
      (libsource (lib "eagle-import") (part "R-US_R0402"))
    )
    (comp (ref "R23")
      (value "10k")
      (footprint "eagle-import:R0402")
      (libsource (lib "eagle-import") (part "R-US_R0402"))
    )
    (comp (ref "R24")
      (value "100k")
      (footprint "eagle-import:R0402")
      (libsource (lib "eagle-import") (part "R-US_R0402"))
    )
    (comp (ref "R25")
      (value "100k")
      (footprint "eagle-import:R0402")
      (libsource (lib "eagle-import") (part "R-US_R0402"))
    )
    (comp (ref "R26")
      (value "100k")
      (footprint "eagle-import:R0402")
      (libsource (lib "eagle-import") (part "R-US_R0402"))
    )
    (comp (ref "R27")
      (value "100k")
      (footprint "eagle-import:R0402")
      (libsource (lib "eagle-import") (part "R-US_R0402"))
    )
    (comp (ref "R28")
      (value "200k")
      (footprint "eagle-import:R0402")
      (libsource (lib "eagle-import") (part "R-US_R0402"))
    )
    (comp (ref "R29")
      (value "200k")
      (footprint "eagle-import:R0402")
      (libsource (lib "eagle-import") (part "R-US_R0402"))
    )
    (comp (ref "R30")
      (value "200k")
      (footprint "eagle-import:R0402")
      (libsource (lib "eagle-import") (part "R-US_R0402"))
    )
    (comp (ref "R31")
      (value "200k")
      (footprint "eagle-import:R0402")
      (libsource (lib "eagle-import") (part "R-US_R0402"))
    )
    (comp (ref "R32")
      (value "100k")
      (footprint "eagle-import:R0402")
      (libsource (lib "eagle-import") (part "R-US_R0402"))
    )
    (comp (ref "R33")
      (value "100k")
      (footprint "eagle-import:R0402")
      (libsource (lib "eagle-import") (part "R-US_R0402"))
    )
    (comp (ref "R34")
      (value "100k")
      (footprint "eagle-import:R0402")
      (libsource (lib "eagle-import") (part "R-US_R0402"))
    )
    (comp (ref "R35")
      (value "100k")
      (footprint "eagle-import:R0402")
      (libsource (lib "eagle-import") (part "R-US_R0402"))
    )
    (comp (ref "R39")
      (value "33k")
      (footprint "eagle-import:R0402")
      (libsource (lib "eagle-import") (part "R-US_R0402"))
    )
    (comp (ref "R40")
      (value "33k")
      (footprint "eagle-import:R0402")
      (libsource (lib "eagle-import") (part "R-US_R0402"))
    )
    (comp (ref "R41")
      (value "33k")
      (footprint "eagle-import:R0402")
      (libsource (lib "eagle-import") (part "R-US_R0402"))
    )
    (comp (ref "R42")
      (value "33k")
      (footprint "eagle-import:R0402")
      (libsource (lib "eagle-import") (part "R-US_R0402"))
    )
    (comp (ref "R57")
      (value "33k")
      (footprint "eagle-import:R0402")
      (libsource (lib "eagle-import") (part "R-US_R0402"))
    )
    (comp (ref "R58")
      (value "33k")
      (footprint "eagle-import:R0402")
      (libsource (lib "eagle-import") (part "R-US_R0402"))
    )
    (comp (ref "R59")
      (value "33k")
      (footprint "eagle-import:R0402")
      (libsource (lib "eagle-import") (part "R-US_R0402"))
    )
    (comp (ref "R64")
      (value "100k")
      (footprint "eagle-import:R0402")
      (libsource (lib "eagle-import") (part "R-US_R0402"))
    )
    (comp (ref "R65")
      (value "100k")
      (footprint "eagle-import:R0402")
      (libsource (lib "eagle-import") (part "R-US_R0402"))
    )
    (comp (ref "R66")
      (value "100k")
      (footprint "eagle-import:R0402")
      (libsource (lib "eagle-import") (part "R-US_R0402"))
    )
    (comp (ref "R70")
      (value "200k")
      (footprint "eagle-import:R0402")
      (libsource (lib "eagle-import") (part "R-US_R0402"))
    )
    (comp (ref "R71")
      (value "200k")
      (footprint "eagle-import:R0402")
      (libsource (lib "eagle-import") (part "R-US_R0402"))
    )
    (comp (ref "R72")
      (value "200k")
      (footprint "eagle-import:R0402")
      (libsource (lib "eagle-import") (part "R-US_R0402"))
    )
    (comp (ref "R76")
      (value "100k")
      (footprint "eagle-import:R0402")
      (libsource (lib "eagle-import") (part "R-US_R0402"))
    )
    (comp (ref "R77")
      (value "100k")
      (footprint "eagle-import:R0402")
      (libsource (lib "eagle-import") (part "R-US_R0402"))
    )
    (comp (ref "C1")
      (value "100n")
      (footprint "eagle-import:C0402")
      (libsource (lib "eagle-import") (part "C-USC0402"))
    )
    (comp (ref "C2")
      (value "22u")
      (footprint "eagle-import:PANASONIC_C")
      (libsource (lib "eagle-import") (part "CPOL-USC"))
    )
    (comp (ref "C3")
      (value "22u")
      (footprint "eagle-import:C1206")
      (libsource (lib "eagle-import") (part "C-USC1206"))
    )
    (comp (ref "C5")
      (value "22u")
      (footprint "eagle-import:C1206")
      (libsource (lib "eagle-import") (part "C-USC1206"))
    )
    (comp (ref "C11")
      (value "22u")
      (footprint "eagle-import:PANASONIC_C")
      (libsource (lib "eagle-import") (part "CPOL-USC"))
    )
    (comp (ref "C14")
      (value "22u")
      (footprint "eagle-import:C1206")
      (libsource (lib "eagle-import") (part "C-USC1206"))
    )
    (comp (ref "C22")
      (value "22u")
      (footprint "eagle-import:PANASONIC_C")
      (libsource (lib "eagle-import") (part "CPOL-USC"))
    )
    (comp (ref "C23")
      (value "22u")
      (footprint "eagle-import:PANASONIC_C")
      (libsource (lib "eagle-import") (part "CPOL-USC"))
    )
    (comp (ref "C52")
      (value "470n")
      (footprint "eagle-import:C0402")
      (libsource (lib "eagle-import") (part "C-USC0402"))
    )
    (comp (ref "D1")
      (value "1N5819HW")
      (footprint "eagle-import:SOD123")
      (libsource (lib "eagle-import") (part "DIODE-SOD123"))
    )
    (comp (ref "D2")
      (value "1N5819HW")
      (footprint "eagle-import:SOD123")
      (libsource (lib "eagle-import") (part "DIODE-SOD123"))
    )
    (comp (ref "H3")
      (value "MOUNT-HOLE3.0TINY")
      (footprint "eagle-import:3,0TINY")
      (libsource (lib "eagle-import") (part "MOUNT-HOLE3.0TINY"))
    )
    (comp (ref "H5")
      (value "MOUNT-HOLE3.0TINY")
      (footprint "eagle-import:3,0TINY")
      (libsource (lib "eagle-import") (part "MOUNT-HOLE3.0TINY"))
    )
    (comp (ref "IC1")
      (value "R-78E3.3-0.5")
      (footprint "eagle-import:WE78")
      (libsource (lib "eagle-import") (part "WE173950378"))
    )
    (comp (ref "IC3")
      (value "LD2981ABU33")
      (footprint "eagle-import:SOT89")
      (libsource (lib "eagle-import") (part "LD2981ABU"))
    )
    (comp (ref "IC8")
      (value "LM4040B10")
      (footprint "eagle-import:DBZ_R-PDSO-G3")
      (libsource (lib "eagle-import") (part "LM4041DBZB12"))
    )
    (comp (ref "JP4")
      (value "M05X2SHD")
      (footprint "eagle-import:2X5-SHROUDED")
      (libsource (lib "eagle-import") (part "M05X2SHD"))
    )
    (comp (ref "L1")
      (value "33u")
      (footprint "eagle-import:L2012C")
      (libsource (lib "eagle-import") (part "L-USL2012C"))
    )
    (comp (ref "L2")
      (value "WE-CBF_0603")
      (footprint "eagle-import:0603")
      (libsource (lib "eagle-import") (part "WE-CBF_0603"))
    )
    (comp (ref "L3")
      (value "WE-CBF_0603")
      (footprint "eagle-import:0603")
      (libsource (lib "eagle-import") (part "WE-CBF_0603"))
    )
    (comp (ref "L4")
      (value "WE-CBF_0603")
      (footprint "eagle-import:0603")
      (libsource (lib "eagle-import") (part "WE-CBF_0603"))
    )
    (comp (ref "R68")
      (value "1.0k")
      (footprint "eagle-import:R0402")
      (libsource (lib "eagle-import") (part "R-US_R0402"))
    )
  )
  (nets
    (net (code "1") (name "+3V3") (class "Default")
      (node (ref "C1") (pin "1") (pinfunction "1_1") (pintype "passive"))
      (node (ref "C12") (pin "1") (pinfunction "1_1") (pintype "passive"))
      (node (ref "C13") (pin "1") (pinfunction "1_1") (pintype "passive"))
      (node (ref "C16") (pin "1") (pinfunction "1_1") (pintype "passive"))
      (node (ref "C19") (pin "1") (pinfunction "1_1") (pintype "passive"))
      (node (ref "C2") (pin "+") (pinfunction "+_+") (pintype "passive"))
      (node (ref "C21") (pin "1") (pinfunction "1_1") (pintype "passive"))
      (node (ref "D3") (pin "2") (pinfunction "C_2") (pintype "passive"))
      (node (ref "IC1") (pin "3") (pinfunction "VO_3") (pintype "passive"))
      (node (ref "IC2") (pin "1") (pinfunction "VBAT_1") (pintype "power_in"))
      (node (ref "IC2") (pin "19") (pinfunction "VDD_4_19") (pintype "power_in"))
      (node (ref "IC2") (pin "32") (pinfunction "VDD_1_32") (pintype "power_in"))
      (node (ref "IC2") (pin "48") (pinfunction "VDD_2_48") (pintype "power_in"))
      (node (ref "IC2") (pin "64") (pinfunction "VDD_3_64") (pintype "power_in"))
      (node (ref "IC4") (pin "12") (pinfunction "DVDD_12") (pintype "power_in"))
      (node (ref "R22") (pin "2") (pinfunction "2_2") (pintype "passive"))
      (node (ref "R23") (pin "2") (pinfunction "2_2") (pintype "passive"))
      (node (ref "R6") (pin "2") (pinfunction "2_2") (pintype "passive"))
    )
    (net (code "2") (name "+3V3_A") (class "Default")
      (node (ref "C10") (pin "1") (pinfunction "1_1") (pintype "passive"))
      (node (ref "C23") (pin "+") (pinfunction "+_+") (pintype "passive"))
      (node (ref "C26") (pin "1") (pinfunction "1_1") (pintype "passive"))
      (node (ref "C27") (pin "+") (pinfunction "+_+") (pintype "passive"))
      (node (ref "C46") (pin "1") (pinfunction "1_1") (pintype "passive"))
      (node (ref "C47") (pin "1") (pinfunction "1_1") (pintype "passive"))
      (node (ref "C9") (pin "1") (pinfunction "1_1") (pintype "passive"))
      (node (ref "IC2") (pin "13") (pinfunction "VDDA_13") (pintype "power_in"))
      (node (ref "IC3") (pin "1") (pinfunction "VO_1") (pintype "passive"))
      (node (ref "IC4") (pin "4") (pinfunction "AVDD_4") (pintype "power_in"))
      (node (ref "IC5") (pin "4") (pinfunction "V+_4") (pintype "power_in"))
      (node (ref "IC6") (pin "4") (pinfunction "V+_4") (pintype "power_in"))
      (node (ref "R13") (pin "P$1") (pinfunction "E_P$1") (pintype "passive"))
      (node (ref "R14") (pin "P$1") (pinfunction "E_P$1") (pintype "passive"))
      (node (ref "R16") (pin "P$1") (pinfunction "E_P$1") (pintype "passive"))
      (node (ref "R20") (pin "P$1") (pinfunction "E_P$1") (pintype "passive"))
      (node (ref "R21") (pin "P$1") (pinfunction "E_P$1") (pintype "passive"))
      (node (ref "R37") (pin "P$1") (pinfunction "E_P$1") (pintype "passive"))
      (node (ref "R38") (pin "P$1") (pinfunction "E_P$1") (pintype "passive"))
      (node (ref "R4") (pin "P$1") (pinfunction "E_P$1") (pintype "passive"))
    )
    (net (code "3") (name "ADC_DV_CV") (class "Default")
      (node (ref "C33") (pin "2") (pinfunction "2_2") (pintype "passive"))
      (node (ref "IC2") (pin "21") (pinfunction "PA5/SPI1_SCK/ADC5/DAC2_21") (pintype "bidirectional"))
      (node (ref "IC6") (pin "8") (pinfunction "OUT_8") (pintype "output"))
      (node (ref "R42") (pin "1") (pinfunction "1_1") (pintype "passive"))
    )
    (net (code "4") (name "ADC_DV_POT") (class "Default")
      (node (ref "C8") (pin "1") (pinfunction "1_1") (pintype "passive"))
      (node (ref "IC2") (pin "11") (pinfunction "PC3/SPI2_MOSI/I2S2_SD/ADC13_11") (pintype "bidirectional"))
      (node (ref "R4") (pin "P$2") (pinfunction "S_P$2") (pintype "passive"))
    )
    (net (code "5") (name "ADC_LENGTH_POT") (class "Default")
      (node (ref "C24") (pin "1") (pinfunction "1_1") (pintype "passive"))
      (node (ref "IC2") (pin "27") (pinfunction "PB1/ADC9/TIM3_CH4_27") (pintype "bidirectional"))
      (node (ref "R16") (pin "P$2") (pinfunction "S_P$2") (pintype "passive"))
    )
    (net (code "6") (name "ADC_T_BIAS_CV") (class "Default")
      (node (ref "C40") (pin "2") (pinfunction "2_2") (pintype "passive"))
      (node (ref "IC2") (pin "15") (pinfunction "PA1/USART2_RTS/UART4_RX/ADC1/TIM2_CH2_15") (pintype "bidirectional"))
      (node (ref "IC5") (pin "1") (pinfunction "OUT_1") (pintype "output"))
      (node (ref "R57") (pin "1") (pinfunction "1_1") (pintype "passive"))
    )
    (net (code "7") (name "ADC_T_BIAS_POT") (class "Default")
      (node (ref "C28") (pin "1") (pinfunction "1_1") (pintype "passive"))
      (node (ref "IC2") (pin "16") (pinfunction "PA2/USART2_TX/ADC2/TIM2_CH3_16") (pintype "bidirectional"))
      (node (ref "R20") (pin "P$2") (pinfunction "S_P$2") (pintype "passive"))
    )
    (net (code "8") (name "ADC_T_JITTER_CV") (class "Default")
      (node (ref "C42") (pin "2") (pinfunction "2_2") (pintype "passive"))
      (node (ref "IC2") (pin "20") (pinfunction "PA4/SPI1_NSS/SPI3_NSS/USART2_CK/I2S3_WS/ADC4/DAC1_20") (pintype "bidirectional"))
      (node (ref "IC6") (pin "7") (pinfunction "OUT_7") (pintype "output"))
      (node (ref "R59") (pin "1") (pinfunction "1_1") (pintype "passive"))
    )
    (net (code "9") (name "ADC_T_JITTER_POT") (class "Default")
      (node (ref "C38") (pin "1") (pinfunction "1_1") (pintype "passive"))
      (node (ref "IC2") (pin "25") (pinfunction "PC5/ADC15_25") (pintype "bidirectional"))
      (node (ref "R37") (pin "P$2") (pinfunction "S_P$2") (pintype "passive"))
    )
    (net (code "10") (name "ADC_T_RATE_CV") (class "Default")
      (node (ref "C41") (pin "2") (pinfunction "2_2") (pintype "passive"))
      (node (ref "IC2") (pin "17") (pinfunction "PA3/USART2_RX/ADC3/TIM2_CH4_17") (pintype "bidirectional"))
      (node (ref "IC6") (pin "1") (pinfunction "OUT_1") (pintype "output"))
      (node (ref "R58") (pin "1") (pinfunction "1_1") (pintype "passive"))
    )
    (net (code "11") (name "ADC_T_RATE_POT") (class "Default")
      (node (ref "C17") (pin "1") (pinfunction "1_1") (pintype "passive"))
      (node (ref "IC2") (pin "10") (pinfunction "PC2/SPI2_MISO/ADC12_10") (pintype "bidirectional"))
      (node (ref "R13") (pin "P$2") (pinfunction "S_P$2") (pintype "passive"))
    )
    (net (code "12") (name "ADC_X_BIAS_CV") (class "Default")
      (node (ref "C30") (pin "2") (pinfunction "2_2") (pintype "passive"))
      (node (ref "IC2") (pin "24") (pinfunction "PC4/ADC14_24") (pintype "bidirectional"))
      (node (ref "IC5") (pin "14") (pinfunction "OUT_14") (pintype "output"))
      (node (ref "R39") (pin "1") (pinfunction "1_1") (pintype "passive"))
    )
    (net (code "13") (name "ADC_X_BIAS_POT") (class "Default")
      (node (ref "C29") (pin "1") (pinfunction "1_1") (pintype "passive"))
      (node (ref "IC2") (pin "9") (pinfunction "PC1/ADC11_9") (pintype "bidirectional"))
      (node (ref "R21") (pin "P$2") (pinfunction "S_P$2") (pintype "passive"))
    )
    (net (code "14") (name "ADC_X_SPREAD_CV") (class "Default")
      (node (ref "C31") (pin "2") (pinfunction "2_2") (pintype "passive"))
      (node (ref "IC2") (pin "14") (pinfunction "PA0-WKUP/USART2_CTS/UART4_TX/ADC0/TIM2_CH1_ETR_14") (pintype "bidirectional"))
      (node (ref "IC2") (pin "23") (pinfunction "PA7/SPI1_MOSI/ADC7/TIM3_CH2_23") (pintype "bidirectional"))
      (node (ref "IC5") (pin "8") (pinfunction "OUT_8") (pintype "output"))
      (node (ref "R40") (pin "1") (pinfunction "1_1") (pintype "passive"))
    )
    (net (code "15") (name "ADC_X_SPREAD_POT") (class "Default")
      (node (ref "C18") (pin "1") (pinfunction "1_1") (pintype "passive"))
      (node (ref "IC2") (pin "8") (pinfunction "PC0/ADC10_8") (pintype "bidirectional"))
      (node (ref "R14") (pin "P$2") (pinfunction "S_P$2") (pintype "passive"))
    )
    (net (code "16") (name "ADC_X_STEPS_CV") (class "Default")
      (node (ref "C32") (pin "2") (pinfunction "2_2") (pintype "passive"))
      (node (ref "IC2") (pin "22") (pinfunction "PA6/SPI1_MISO/ADC6/TIM3_CH1_22") (pintype "bidirectional"))
      (node (ref "IC6") (pin "14") (pinfunction "OUT_14") (pintype "output"))
      (node (ref "R41") (pin "1") (pinfunction "1_1") (pintype "passive"))
    )
    (net (code "17") (name "ADC_X_STEPS_POT") (class "Default")
      (node (ref "C36") (pin "1") (pinfunction "1_1") (pintype "passive"))
      (node (ref "IC2") (pin "26") (pinfunction "PB0/ADC8/TIM3_CH3_26") (pintype "bidirectional"))
      (node (ref "R38") (pin "P$2") (pinfunction "S_P$2") (pintype "passive"))
    )
    (net (code "18") (name "AREF_-10") (class "Default")
      (node (ref "C52") (pin "1") (pinfunction "1_1") (pintype "passive"))
      (node (ref "IC8") (pin "2") (pinfunction "A_2") (pintype "passive"))
      (node (ref "R28") (pin "2") (pinfunction "2_2") (pintype "passive"))
      (node (ref "R29") (pin "2") (pinfunction "2_2") (pintype "passive"))
      (node (ref "R30") (pin "2") (pinfunction "2_2") (pintype "passive"))
      (node (ref "R31") (pin "2") (pinfunction "2_2") (pintype "passive"))
      (node (ref "R68") (pin "2") (pinfunction "2_2") (pintype "passive"))
      (node (ref "R70") (pin "2") (pinfunction "2_2") (pintype "passive"))
      (node (ref "R71") (pin "2") (pinfunction "2_2") (pintype "passive"))
      (node (ref "R72") (pin "2") (pinfunction "2_2") (pintype "passive"))
    )
    (net (code "19") (name "DAC_MOSI") (class "Default")
      (node (ref "IC2") (pin "53") (pinfunction "PC12/UART5_TX/I2S3_SD/USART3_CK_53") (pintype "bidirectional"))
      (node (ref "IC4") (pin "11") (pinfunction "IN_11") (pintype "input"))
    )
    (net (code "20") (name "DAC_SCK") (class "Default")
      (node (ref "IC2") (pin "51") (pinfunction "PC10/SPI3_SCK/I2S3_SCK/UART4_TX_51") (pintype "bidirectional"))
      (node (ref "IC4") (pin "10") (pinfunction "SCK_10") (pintype "input"))
    )
    (net (code "21") (name "DAC_SS") (class "Default")
      (node (ref "IC2") (pin "50") (pinfunction "PA15/JTDI/SPI3_NSS/I2S3_WS_50") (pintype "bidirectional"))
      (node (ref "IC4") (pin "9") (pinfunction "SYNC_9") (pintype "input"))
    )
    (net (code "22") (name "DAC_X_1") (class "Default")
      (node (ref "IC4") (pin "2") (pinfunction "OUTB_2") (pintype "output"))
      (node (ref "R47") (pin "2") (pinfunction "2_2") (pintype "passive"))
    )
    (net (code "23") (name "DAC_X_2") (class "Default")
      (node (ref "IC4") (pin "7") (pinfunction "OUTC_7") (pintype "output"))
      (node (ref "R48") (pin "2") (pinfunction "2_2") (pintype "passive"))
    )
    (net (code "24") (name "DAC_X_3") (class "Default")
      (node (ref "IC4") (pin "8") (pinfunction "OUTD_8") (pintype "output"))
      (node (ref "R53") (pin "2") (pinfunction "2_2") (pintype "passive"))
    )
    (net (code "25") (name "DAC_Y") (class "Default")
      (node (ref "IC4") (pin "1") (pinfunction "OUTA_1") (pintype "output"))
      (node (ref "R54") (pin "2") (pinfunction "2_2") (pintype "passive"))
    )
    (net (code "26") (name "DEPRECATED") (class "Default")
      (node (ref "IC5") (pin "6") (pinfunction "-IN_6") (pintype "input"))
      (node (ref "IC5") (pin "7") (pinfunction "OUT_7") (pintype "output"))
    )
    (net (code "27") (name "GATE_T_1") (class "Default")
      (node (ref "IC2") (pin "52") (pinfunction "PC11/UART4_RX/SPI3_MISO/USART3_RX_52") (pintype "bidirectional"))
      (node (ref "LED6") (pin "1") (pinfunction "1_1") (pintype "bidirectional"))
      (node (ref "R56") (pin "2") (pinfunction "2_2") (pintype "passive"))
    )
    (net (code "28") (name "GATE_T_2") (class "Default")
      (node (ref "IC2") (pin "44") (pinfunction "PA11/USART1_CTS/CANRX/USBDM/TIM1_CH4_44") (pintype "bidirectional"))
      (node (ref "LED7") (pin "1") (pinfunction "1_1") (pintype "bidirectional"))
      (node (ref "R55") (pin "2") (pinfunction "2_2") (pintype "passive"))
    )
    (net (code "29") (name "GATE_T_3") (class "Default")
      (node (ref "IC2") (pin "45") (pinfunction "PA12/USART1_RTS/CANTX/USBDP/TIM1_ETR_45") (pintype "bidirectional"))
      (node (ref "LED8") (pin "1") (pinfunction "1_1") (pintype "bidirectional"))
      (node (ref "R67") (pin "2") (pinfunction "2_2") (pintype "passive"))
    )
    (net (code "30") (name "GND") (class "Default")
      (node (ref "C1") (pin "2") (pinfunction "2_2") (pintype "passive"))
      (node (ref "C10") (pin "2") (pinfunction "2_2") (pintype "passive"))
      (node (ref "C11") (pin "-") (pinfunction "-_-") (pintype "passive"))
      (node (ref "C12") (pin "2") (pinfunction "2_2") (pintype "passive"))
      (node (ref "C13") (pin "2") (pinfunction "2_2") (pintype "passive"))
      (node (ref "C14") (pin "2") (pinfunction "2_2") (pintype "passive"))
      (node (ref "C15") (pin "2") (pinfunction "2_2") (pintype "passive"))
      (node (ref "C16") (pin "2") (pinfunction "2_2") (pintype "passive"))
      (node (ref "C17") (pin "2") (pinfunction "2_2") (pintype "passive"))
      (node (ref "C18") (pin "2") (pinfunction "2_2") (pintype "passive"))
      (node (ref "C19") (pin "2") (pinfunction "2_2") (pintype "passive"))
      (node (ref "C2") (pin "-") (pinfunction "-_-") (pintype "passive"))
      (node (ref "C20") (pin "2") (pinfunction "2_2") (pintype "passive"))
      (node (ref "C21") (pin "2") (pinfunction "2_2") (pintype "passive"))
      (node (ref "C22") (pin "+") (pinfunction "+_+") (pintype "passive"))
      (node (ref "C23") (pin "-") (pinfunction "-_-") (pintype "passive"))
      (node (ref "C24") (pin "2") (pinfunction "2_2") (pintype "passive"))
      (node (ref "C25") (pin "2") (pinfunction "2_2") (pintype "passive"))
      (node (ref "C26") (pin "2") (pinfunction "2_2") (pintype "passive"))
      (node (ref "C27") (pin "-") (pinfunction "-_-") (pintype "passive"))
      (node (ref "C28") (pin "2") (pinfunction "2_2") (pintype "passive"))
      (node (ref "C29") (pin "2") (pinfunction "2_2") (pintype "passive"))
      (node (ref "C3") (pin "2") (pinfunction "2_2") (pintype "passive"))
      (node (ref "C36") (pin "2") (pinfunction "2_2") (pintype "passive"))
      (node (ref "C37") (pin "1") (pinfunction "1_1") (pintype "passive"))
      (node (ref "C38") (pin "2") (pinfunction "2_2") (pintype "passive"))
      (node (ref "C39") (pin "2") (pinfunction "2_2") (pintype "passive"))
      (node (ref "C4") (pin "1") (pinfunction "1_1") (pintype "passive"))
      (node (ref "C45") (pin "2") (pinfunction "2_2") (pintype "passive"))
      (node (ref "C46") (pin "2") (pinfunction "2_2") (pintype "passive"))
      (node (ref "C47") (pin "2") (pinfunction "2_2") (pintype "passive"))
      (node (ref "C48") (pin "2") (pinfunction "2_2") (pintype "passive"))
      (node (ref "C49") (pin "1") (pinfunction "1_1") (pintype "passive"))
      (node (ref "C5") (pin "2") (pinfunction "2_2") (pintype "passive"))
      (node (ref "C50") (pin "2") (pinfunction "2_2") (pintype "passive"))
      (node (ref "C51") (pin "2") (pinfunction "2_2") (pintype "passive"))
      (node (ref "C52") (pin "2") (pinfunction "2_2") (pintype "passive"))
      (node (ref "C53") (pin "2") (pinfunction "2_2") (pintype "passive"))
      (node (ref "C54") (pin "2") (pinfunction "2_2") (pintype "passive"))
      (node (ref "C55") (pin "2") (pinfunction "2_2") (pintype "passive"))
      (node (ref "C56") (pin "2") (pinfunction "2_2") (pintype "passive"))
      (node (ref "C57") (pin "2") (pinfunction "2_2") (pintype "passive"))
      (node (ref "C58") (pin "2") (pinfunction "2_2") (pintype "passive"))
      (node (ref "C6") (pin "1") (pinfunction "1_1") (pintype "passive"))
      (node (ref "C7") (pin "2") (pinfunction "2_2") (pintype "passive"))
      (node (ref "C8") (pin "2") (pinfunction "2_2") (pintype "passive"))
      (node (ref "C9") (pin "2") (pinfunction "2_2") (pintype "passive"))
      (node (ref "D3") (pin "1") (pinfunction "A_1") (pintype "passive"))
      (node (ref "D4") (pin "A") (pinfunction "A_A") (pintype "passive"))
      (node (ref "D5") (pin "A") (pinfunction "A_A") (pintype "passive"))
      (node (ref "IC1") (pin "2") (pinfunction "GND_2") (pintype "passive"))
      (node (ref "IC2") (pin "12") (pinfunction "VSSA_12") (pintype "power_in"))
      (node (ref "IC2") (pin "18") (pinfunction "VSS_4_18") (pintype "power_in"))
      (node (ref "IC2") (pin "28") (pinfunction "PB2/BOOT1_28") (pintype "bidirectional"))
      (node (ref "IC2") (pin "60") (pinfunction "BOOT0_60") (pintype "bidirectional"))
      (node (ref "IC2") (pin "63") (pinfunction "VSS_3_63") (pintype "power_in"))
      (node (ref "IC3") (pin "2") (pinfunction "GND_2") (pintype "passive"))
      (node (ref "IC4") (pin "13") (pinfunction "A0_13") (pintype "input"))
      (node (ref "IC4") (pin "14") (pinfunction "A1_14") (pintype "input"))
      (node (ref "IC4") (pin "15") (pinfunction "ENABLE_15") (pintype "input"))
      (node (ref "IC4") (pin "16") (pinfunction "LDAC_16") (pintype "input"))
      (node (ref "IC4") (pin "5") (pinfunction "VREFL_5") (pintype "bidirectional"))
      (node (ref "IC4") (pin "6") (pinfunction "GND_6") (pintype "power_in"))
      (node (ref "IC5") (pin "10") (pinfunction "+IN_10") (pintype "input"))
      (node (ref "IC5") (pin "11") (pinfunction "V-_11") (pintype "power_in"))
      (node (ref "IC5") (pin "12") (pinfunction "+IN_12") (pintype "input"))
      (node (ref "IC5") (pin "3") (pinfunction "+IN_3") (pintype "input"))
      (node (ref "IC5") (pin "5") (pinfunction "+IN_5") (pintype "input"))
      (node (ref "IC6") (pin "10") (pinfunction "+IN_10") (pintype "input"))
      (node (ref "IC6") (pin "11") (pinfunction "V-_11") (pintype "power_in"))
      (node (ref "IC6") (pin "12") (pinfunction "+IN_12") (pintype "input"))
      (node (ref "IC6") (pin "3") (pinfunction "+IN_3") (pintype "input"))
      (node (ref "IC6") (pin "5") (pinfunction "+IN_5") (pintype "input"))
      (node (ref "IC8") (pin "1") (pinfunction "C_1") (pintype "passive"))
      (node (ref "IC9") (pin "11") (pinfunction "V-_11") (pintype "power_in"))
      (node (ref "IC9") (pin "5") (pinfunction "+IN_5") (pintype "input"))
      (node (ref "J1") (pin "P1") (pinfunction "1_P1") (pintype "passive"))
      (node (ref "J1") (pin "P2") (pinfunction "2_P2") (pintype "passive"))
      (node (ref "J10") (pin "P1") (pinfunction "1_P1") (pintype "passive"))
      (node (ref "J11") (pin "P1") (pinfunction "1_P1") (pintype "passive"))
      (node (ref "J12") (pin "P1") (pinfunction "1_P1") (pintype "passive"))
      (node (ref "J13") (pin "P1") (pinfunction "1_P1") (pintype "passive"))
      (node (ref "J14") (pin "P1") (pinfunction "1_P1") (pintype "passive"))
      (node (ref "J15") (pin "P1") (pinfunction "1_P1") (pintype "passive"))
      (node (ref "J16") (pin "P1") (pinfunction "1_P1") (pintype "passive"))
      (node (ref "J2") (pin "P1") (pinfunction "1_P1") (pintype "passive"))
      (node (ref "J2") (pin "P2") (pinfunction "2_P2") (pintype "passive"))
      (node (ref "J3") (pin "P1") (pinfunction "1_P1") (pintype "passive"))
      (node (ref "J4") (pin "P1") (pinfunction "1_P1") (pintype "passive"))
      (node (ref "J4") (pin "P2") (pinfunction "2_P2") (pintype "passive"))
      (node (ref "J5") (pin "P1") (pinfunction "1_P1") (pintype "passive"))
      (node (ref "J5") (pin "P2") (pinfunction "2_P2") (pintype "passive"))
      (node (ref "J6") (pin "P1") (pinfunction "1_P1") (pintype "passive"))
      (node (ref "J6") (pin "P2") (pinfunction "2_P2") (pintype "passive"))
      (node (ref "J7") (pin "P1") (pinfunction "1_P1") (pintype "passive"))
      (node (ref "J7") (pin "P2") (pinfunction "2_P2") (pintype "passive"))
      (node (ref "J8") (pin "P1") (pinfunction "1_P1") (pintype "passive"))
      (node (ref "J8") (pin "P2") (pinfunction "2_P2") (pintype "passive"))
      (node (ref "J9") (pin "P1") (pinfunction "1_P1") (pintype "passive"))
      (node (ref "JP1") (pin "1") (pinfunction "1_1") (pintype "passive"))
      (node (ref "JP4") (pin "3") (pinfunction "3_3") (pintype "passive"))
      (node (ref "JP4") (pin "4") (pinfunction "4_4") (pintype "passive"))
      (node (ref "JP4") (pin "5") (pinfunction "5_5") (pintype "passive"))
      (node (ref "JP4") (pin "6") (pinfunction "6_6") (pintype "passive"))
      (node (ref "JP4") (pin "7") (pinfunction "7_7") (pintype "passive"))
      (node (ref "JP4") (pin "8") (pinfunction "8_8") (pintype "passive"))
      (node (ref "LED1") (pin "2") (pinfunction "C_2") (pintype "bidirectional"))
      (node (ref "LED2") (pin "2") (pinfunction "C_2") (pintype "bidirectional"))
      (node (ref "LED3") (pin "2") (pinfunction "C_2") (pintype "bidirectional"))
      (node (ref "LED4") (pin "2") (pinfunction "C_2") (pintype "bidirectional"))
      (node (ref "LED5") (pin "2") (pinfunction "C_2") (pintype "bidirectional"))
      (node (ref "Q1") (pin "2") (pinfunction "LID1_2") (pintype "power_in"))
      (node (ref "Q1") (pin "4") (pinfunction "LID2_4") (pintype "power_in"))
      (node (ref "Q2") (pin "E") (pinfunction "E_E") (pintype "passive"))
      (node (ref "Q3") (pin "E") (pinfunction "E_E") (pintype "passive"))
      (node (ref "R13") (pin "P$3") (pinfunction "A_P$3") (pintype "passive"))
      (node (ref "R14") (pin "P$3") (pinfunction "A_P$3") (pintype "passive"))
      (node (ref "R16") (pin "P$3") (pinfunction "A_P$3") (pintype "passive"))
      (node (ref "R20") (pin "P$3") (pinfunction "A_P$3") (pintype "passive"))
      (node (ref "R21") (pin "P$3") (pinfunction "A_P$3") (pintype "passive"))
      (node (ref "R24") (pin "1") (pinfunction "1_1") (pintype "passive"))
      (node (ref "R25") (pin "1") (pinfunction "1_1") (pintype "passive"))
      (node (ref "R37") (pin "P$3") (pinfunction "A_P$3") (pintype "passive"))
      (node (ref "R38") (pin "P$3") (pinfunction "A_P$3") (pintype "passive"))
      (node (ref "R4") (pin "P$3") (pinfunction "A_P$3") (pintype "passive"))
      (node (ref "R49") (pin "2") (pinfunction "2_2") (pintype "passive"))
      (node (ref "R50") (pin "2") (pinfunction "2_2") (pintype "passive"))
      (node (ref "R73") (pin "1") (pinfunction "1_1") (pintype "passive"))
      (node (ref "R75") (pin "2") (pinfunction "2_2") (pintype "passive"))
      (node (ref "R78") (pin "2") (pinfunction "2_2") (pintype "passive"))
      (node (ref "R79") (pin "2") (pinfunction "2_2") (pintype "passive"))
      (node (ref "R80") (pin "2") (pinfunction "2_2") (pintype "passive"))
      (node (ref "R81") (pin "2") (pinfunction "2_2") (pintype "passive"))
      (node (ref "R82") (pin "1") (pinfunction "1_1") (pintype "passive"))
      (node (ref "R83") (pin "1") (pinfunction "1_1") (pintype "passive"))
      (node (ref "R84") (pin "1") (pinfunction "1_1") (pintype "passive"))
      (node (ref "SW1") (pin "L2") (pinfunction "L2_L2") (pintype "passive"))
      (node (ref "SW1") (pin "P3") (pinfunction "A3_P3") (pintype "passive"))
      (node (ref "SW1") (pin "P6") (pinfunction "B3_P6") (pintype "passive"))
      (node (ref "SW2") (pin "L2") (pinfunction "L2_L2") (pintype "passive"))
      (node (ref "SW2") (pin "P3") (pinfunction "A3_P3") (pintype "passive"))
      (node (ref "SW2") (pin "P6") (pinfunction "B3_P6") (pintype "passive"))
      (node (ref "SW3") (pin "1") (pinfunction "1_1") (pintype "passive"))
      (node (ref "SW3") (pin "2") (pinfunction "2_2") (pintype "passive"))
      (node (ref "SW4") (pin "1") (pinfunction "1_1") (pintype "passive"))
      (node (ref "SW4") (pin "2") (pinfunction "2_2") (pintype "passive"))
      (node (ref "SW5") (pin "1") (pinfunction "1_1") (pintype "passive"))
      (node (ref "SW5") (pin "2") (pinfunction "2_2") (pintype "passive"))
      (node (ref "SW6") (pin "1") (pinfunction "1_1") (pintype "passive"))
      (node (ref "SW6") (pin "2") (pinfunction "2_2") (pintype "passive"))
      (node (ref "SW7") (pin "1") (pinfunction "1_1") (pintype "passive"))
      (node (ref "SW7") (pin "2") (pinfunction "2_2") (pintype "passive"))
    )
    (net (code "31") (name "LED_T_DV") (class "Default")
      (node (ref "IC2") (pin "29") (pinfunction "PB10/SPI2_SCK/I2S_SCK/I2C2_SCL/USART3_TX_29") (pintype "bidirectional"))
      (node (ref "R1") (pin "1") (pinfunction "1_1") (pintype "passive"))
    )
    (net (code "32") (name "LED_T_MODE_G") (class "Default")
      (node (ref "IC2") (pin "33") (pinfunction "PB12/SPI2_NSS/I2S2_WS/I2C2_SMBA/USART3_CK/TIM1_BKIN_33") (pintype "bidirectional"))
      (node (ref "R10") (pin "1") (pinfunction "1_1") (pintype "passive"))
    )
    (net (code "33") (name "LED_T_MODE_R") (class "Default")
      (node (ref "IC2") (pin "34") (pinfunction "PB13/SPI2_SCK/I2S2_SCK/USART3_CTS/TIM1_CH1N_34") (pintype "bidirectional"))
      (node (ref "R9") (pin "1") (pinfunction "1_1") (pintype "passive"))
    )
    (net (code "34") (name "LED_T_RANGE_G") (class "Default")
      (node (ref "IC2") (pin "37") (pinfunction "PC6/I2S2_MCK_37") (pintype "bidirectional"))
      (node (ref "R18") (pin "1") (pinfunction "1_1") (pintype "passive"))
    )
    (net (code "35") (name "LED_T_RANGE_R") (class "Default")
      (node (ref "IC2") (pin "38") (pinfunction "PC7/I2S3_MCK_38") (pintype "bidirectional"))
      (node (ref "R19") (pin "1") (pinfunction "1_1") (pintype "passive"))
    )
    (net (code "36") (name "LED_X_DV") (class "Default")
      (node (ref "IC2") (pin "62") (pinfunction "PB9/SPI2_NSS/I2S2_WS/I2C1_SDA/TIM4_CH4_62") (pintype "bidirectional"))
      (node (ref "R5") (pin "1") (pinfunction "1_1") (pintype "passive"))
    )
    (net (code "37") (name "LED_X_EXT_G") (class "Default")
      (node (ref "IC2") (pin "55") (pinfunction "PB3/JTDO/SPI3_SCK/I2S3_SCK_55") (pintype "bidirectional"))
      (node (ref "R36") (pin "1") (pinfunction "1_1") (pintype "passive"))
    )
    (net (code "38") (name "LED_X_MODE_G") (class "Default")
      (node (ref "IC2") (pin "59") (pinfunction "PB7/I2C1_SDA/TIM4_CH2/USART1_RX_59") (pintype "bidirectional"))
      (node (ref "R12") (pin "1") (pinfunction "1_1") (pintype "passive"))
    )
    (net (code "39") (name "LED_X_MODE_R") (class "Default")
      (node (ref "IC2") (pin "61") (pinfunction "PB8/TIM4_CH3/I2C1_SCL_61") (pintype "bidirectional"))
      (node (ref "R11") (pin "1") (pinfunction "1_1") (pintype "passive"))
    )
    (net (code "40") (name "LED_X_RANGE_G") (class "Default")
      (node (ref "IC2") (pin "57") (pinfunction "PB5/I2C1_SMBA/SPI1_MOSI/SPI3_MOSI/I2S3_SD_57") (pintype "bidirectional"))
      (node (ref "R17") (pin "1") (pinfunction "1_1") (pintype "passive"))
    )
    (net (code "41") (name "LED_X_RANGE_R") (class "Default")
      (node (ref "IC2") (pin "56") (pinfunction "PB4/NJTRST/SPI3_MISO/SPI1_MISO_56") (pintype "bidirectional"))
      (node (ref "R15") (pin "1") (pinfunction "1_1") (pintype "passive"))
    )
    (net (code "42") (name "NORMALIZATION_PROBE") (class "Default")
      (node (ref "D3") (pin "3") (pinfunction "AC_3") (pintype "passive"))
      (node (ref "IC2") (pin "39") (pinfunction "PC8_39") (pintype "bidirectional"))
      (node (ref "R76") (pin "1") (pinfunction "1_1") (pintype "passive"))
      (node (ref "R77") (pin "1") (pinfunction "1_1") (pintype "passive"))
    )
    (net (code "43") (name "Net-(C5-Pad1)") (class "Default")
      (node (ref "C5") (pin "1") (pinfunction "1_1") (pintype "passive"))
      (node (ref "D1") (pin "C") (pinfunction "C_C") (pintype "passive"))
      (node (ref "L1") (pin "1") (pinfunction "1_1") (pintype "passive"))
      (node (ref "L2") (pin "2") (pinfunction "2_2") (pintype "passive"))
      (node (ref "L3") (pin "2") (pinfunction "2_2") (pintype "passive"))
    )
    (net (code "44") (name "Net-(C6-Pad2)") (class "Default")
      (node (ref "C6") (pin "2") (pinfunction "2_2") (pintype "passive"))
      (node (ref "Q1") (pin "1") (pinfunction "1_1") (pintype "passive"))
      (node (ref "R7") (pin "2") (pinfunction "2_2") (pintype "passive"))
    )
    (net (code "45") (name "Net-(D1-PadA)") (class "Default")
      (node (ref "D1") (pin "A") (pinfunction "A_A") (pintype "passive"))
      (node (ref "JP4") (pin "10") (pinfunction "10_10") (pintype "passive"))
      (node (ref "JP4") (pin "9") (pinfunction "9_9") (pintype "passive"))
    )
    (net (code "46") (name "Net-(D2-PadA)") (class "Default")
      (node (ref "D2") (pin "A") (pinfunction "A_A") (pintype "passive"))
      (node (ref "L4") (pin "2") (pinfunction "2_2") (pintype "passive"))
    )
    (net (code "47") (name "Net-(D2-PadC)") (class "Default")
      (node (ref "D2") (pin "C") (pinfunction "C_C") (pintype "passive"))
      (node (ref "JP4") (pin "1") (pinfunction "1_1") (pintype "passive"))
      (node (ref "JP4") (pin "2") (pinfunction "2_2") (pintype "passive"))
    )
    (net (code "48") (name "Net-(D4-PadC)") (class "Default")
      (node (ref "D4") (pin "C") (pinfunction "C_C") (pintype "passive"))
      (node (ref "Q2") (pin "B") (pinfunction "B_B") (pintype "passive"))
      (node (ref "R24") (pin "2") (pinfunction "2_2") (pintype "passive"))
      (node (ref "R26") (pin "2") (pinfunction "2_2") (pintype "passive"))
    )
    (net (code "49") (name "Net-(D5-PadC)") (class "Default")
      (node (ref "D5") (pin "C") (pinfunction "C_C") (pintype "passive"))
      (node (ref "Q3") (pin "B") (pinfunction "B_B") (pintype "passive"))
      (node (ref "R25") (pin "2") (pinfunction "2_2") (pintype "passive"))
      (node (ref "R27") (pin "2") (pinfunction "2_2") (pintype "passive"))
    )
    (net (code "50") (name "Net-(IC1-VI)") (class "Default")
      (node (ref "C3") (pin "1") (pinfunction "1_1") (pintype "passive"))
      (node (ref "IC1") (pin "1") (pinfunction "VI_1") (pintype "input"))
      (node (ref "L1") (pin "2") (pinfunction "2_2") (pintype "passive"))
    )
    (net (code "51") (name "Net-(IC2-PD0{slash}OSC_IN)") (class "Default")
      (node (ref "IC2") (pin "5") (pinfunction "PD0/OSC_IN_5") (pintype "bidirectional"))
      (node (ref "R8") (pin "1") (pinfunction "1_1") (pintype "passive"))
    )
    (net (code "52") (name "Net-(IC2-PD1{slash}OSC_OUT)") (class "Default")
      (node (ref "IC2") (pin "6") (pinfunction "PD1/OSC_OUT_6") (pintype "bidirectional"))
      (node (ref "R7") (pin "1") (pinfunction "1_1") (pintype "passive"))
    )
    (net (code "53") (name "Net-(IC2-VCAP_1)") (class "Default")
      (node (ref "C15") (pin "1") (pinfunction "1_1") (pintype "passive"))
      (node (ref "IC2") (pin "31") (pinfunction "VCAP_1_31") (pintype "power_in"))
    )
    (net (code "54") (name "Net-(IC2-VCAP_2)") (class "Default")
      (node (ref "C20") (pin "1") (pinfunction "1_1") (pintype "passive"))
      (node (ref "IC2") (pin "47") (pinfunction "VCAP_2_47") (pintype "power_in"))
    )
    (net (code "55") (name "Net-(IC3-VI)") (class "Default")
      (node (ref "C14") (pin "1") (pinfunction "1_1") (pintype "passive"))
      (node (ref "IC3") (pin "3") (pinfunction "VI_3") (pintype "input"))
      (node (ref "L3") (pin "1") (pinfunction "1_1") (pintype "passive"))
    )
    (net (code "56") (name "Net-(IC5A--IN)") (class "Default")
      (node (ref "C40") (pin "1") (pinfunction "1_1") (pintype "passive"))
      (node (ref "IC5") (pin "2") (pinfunction "-IN_2") (pintype "input"))
      (node (ref "R57") (pin "2") (pinfunction "2_2") (pintype "passive"))
      (node (ref "R64") (pin "1") (pinfunction "1_1") (pintype "passive"))
      (node (ref "R70") (pin "1") (pinfunction "1_1") (pintype "passive"))
    )
    (net (code "57") (name "Net-(IC5C--IN)") (class "Default")
      (node (ref "C31") (pin "1") (pinfunction "1_1") (pintype "passive"))
      (node (ref "IC5") (pin "9") (pinfunction "-IN_9") (pintype "input"))
      (node (ref "R28") (pin "1") (pinfunction "1_1") (pintype "passive"))
      (node (ref "R34") (pin "1") (pinfunction "1_1") (pintype "passive"))
      (node (ref "R40") (pin "2") (pinfunction "2_2") (pintype "passive"))
    )
    (net (code "58") (name "Net-(IC5D--IN)") (class "Default")
      (node (ref "C30") (pin "1") (pinfunction "1_1") (pintype "passive"))
      (node (ref "IC5") (pin "13") (pinfunction "-IN_13") (pintype "input"))
      (node (ref "R30") (pin "1") (pinfunction "1_1") (pintype "passive"))
      (node (ref "R33") (pin "1") (pinfunction "1_1") (pintype "passive"))
      (node (ref "R39") (pin "2") (pinfunction "2_2") (pintype "passive"))
    )
    (net (code "59") (name "Net-(IC6A--IN)") (class "Default")
      (node (ref "C41") (pin "1") (pinfunction "1_1") (pintype "passive"))
      (node (ref "IC6") (pin "2") (pinfunction "-IN_2") (pintype "input"))
      (node (ref "R58") (pin "2") (pinfunction "2_2") (pintype "passive"))
      (node (ref "R65") (pin "1") (pinfunction "1_1") (pintype "passive"))
      (node (ref "R71") (pin "1") (pinfunction "1_1") (pintype "passive"))
    )
    (net (code "60") (name "Net-(IC6B--IN)") (class "Default")
      (node (ref "C42") (pin "1") (pinfunction "1_1") (pintype "passive"))
      (node (ref "IC6") (pin "6") (pinfunction "-IN_6") (pintype "input"))
      (node (ref "R59") (pin "2") (pinfunction "2_2") (pintype "passive"))
      (node (ref "R66") (pin "1") (pinfunction "1_1") (pintype "passive"))
      (node (ref "R72") (pin "1") (pinfunction "1_1") (pintype "passive"))
    )
    (net (code "61") (name "Net-(IC6C--IN)") (class "Default")
      (node (ref "C33") (pin "1") (pinfunction "1_1") (pintype "passive"))
      (node (ref "IC6") (pin "9") (pinfunction "-IN_9") (pintype "input"))
      (node (ref "R31") (pin "1") (pinfunction "1_1") (pintype "passive"))
      (node (ref "R32") (pin "1") (pinfunction "1_1") (pintype "passive"))
      (node (ref "R42") (pin "2") (pinfunction "2_2") (pintype "passive"))
    )
    (net (code "62") (name "Net-(IC6D--IN)") (class "Default")
      (node (ref "C32") (pin "1") (pinfunction "1_1") (pintype "passive"))
      (node (ref "IC6") (pin "13") (pinfunction "-IN_13") (pintype "input"))
      (node (ref "R29") (pin "1") (pinfunction "1_1") (pintype "passive"))
      (node (ref "R35") (pin "1") (pinfunction "1_1") (pintype "passive"))
      (node (ref "R41") (pin "2") (pinfunction "2_2") (pintype "passive"))
    )
    (net (code "63") (name "Net-(IC7A--IN)") (class "Default")
      (node (ref "C34") (pin "1") (pinfunction "1_1") (pintype "passive"))
      (node (ref "IC7") (pin "2") (pinfunction "-IN_2") (pintype "input"))
      (node (ref "R43") (pin "2") (pinfunction "2_2") (pintype "passive"))
      (node (ref "R47") (pin "1") (pinfunction "1_1") (pintype "passive"))
    )
    (net (code "64") (name "Net-(IC7B--IN)") (class "Default")
      (node (ref "C43") (pin "1") (pinfunction "1_1") (pintype "passive"))
      (node (ref "IC7") (pin "6") (pinfunction "-IN_6") (pintype "input"))
      (node (ref "R54") (pin "1") (pinfunction "1_1") (pintype "passive"))
      (node (ref "R60") (pin "2") (pinfunction "2_2") (pintype "passive"))
    )
    (net (code "65") (name "Net-(IC7C--IN)") (class "Default")
      (node (ref "C44") (pin "1") (pinfunction "1_1") (pintype "passive"))
      (node (ref "IC7") (pin "9") (pinfunction "-IN_9") (pintype "input"))
      (node (ref "R53") (pin "1") (pinfunction "1_1") (pintype "passive"))
      (node (ref "R61") (pin "2") (pinfunction "2_2") (pintype "passive"))
    )
    (net (code "66") (name "Net-(IC7D--IN)") (class "Default")
      (node (ref "C35") (pin "1") (pinfunction "1_1") (pintype "passive"))
      (node (ref "IC7") (pin "13") (pinfunction "-IN_13") (pintype "input"))
      (node (ref "R44") (pin "2") (pinfunction "2_2") (pintype "passive"))
      (node (ref "R48") (pin "1") (pinfunction "1_1") (pintype "passive"))
    )
    (net (code "67") (name "Net-(IC9A-+IN)") (class "Default")
      (node (ref "IC9") (pin "3") (pinfunction "+IN_3") (pintype "input"))
      (node (ref "R56") (pin "1") (pinfunction "1_1") (pintype "passive"))
    )
    (net (code "68") (name "Net-(IC9A--IN)") (class "Default")
      (node (ref "IC9") (pin "2") (pinfunction "-IN_2") (pintype "input"))
      (node (ref "R50") (pin "1") (pinfunction "1_1") (pintype "passive"))
      (node (ref "R51") (pin "2") (pinfunction "2_2") (pintype "passive"))
    )
    (net (code "69") (name "Net-(IC9A-OUT)") (class "Default")
      (node (ref "IC9") (pin "1") (pinfunction "OUT_1") (pintype "output"))
      (node (ref "R51") (pin "1") (pinfunction "1_1") (pintype "passive"))
      (node (ref "R85") (pin "2") (pinfunction "2_2") (pintype "passive"))
    )
    (net (code "70") (name "Net-(IC9B--IN)") (class "Default")
      (node (ref "IC9") (pin "6") (pinfunction "-IN_6") (pintype "input"))
      (node (ref "IC9") (pin "7") (pinfunction "OUT_7") (pintype "output"))
    )
    (net (code "71") (name "Net-(IC9C-+IN)") (class "Default")
      (node (ref "IC9") (pin "10") (pinfunction "+IN_10") (pintype "input"))
      (node (ref "R67") (pin "1") (pinfunction "1_1") (pintype "passive"))
    )
    (net (code "72") (name "Net-(IC9C--IN)") (class "Default")
      (node (ref "IC9") (pin "9") (pinfunction "-IN_9") (pintype "input"))
      (node (ref "R69") (pin "2") (pinfunction "2_2") (pintype "passive"))
      (node (ref "R75") (pin "1") (pinfunction "1_1") (pintype "passive"))
    )
    (net (code "73") (name "Net-(IC9C-OUT)") (class "Default")
      (node (ref "IC9") (pin "8") (pinfunction "OUT_8") (pintype "output"))
      (node (ref "R69") (pin "1") (pinfunction "1_1") (pintype "passive"))
      (node (ref "R87") (pin "2") (pinfunction "2_2") (pintype "passive"))
    )
    (net (code "74") (name "Net-(IC9D-+IN)") (class "Default")
      (node (ref "IC9") (pin "12") (pinfunction "+IN_12") (pintype "input"))
      (node (ref "R55") (pin "1") (pinfunction "1_1") (pintype "passive"))
    )
    (net (code "75") (name "Net-(IC9D--IN)") (class "Default")
      (node (ref "IC9") (pin "13") (pinfunction "-IN_13") (pintype "input"))
      (node (ref "R49") (pin "1") (pinfunction "1_1") (pintype "passive"))
      (node (ref "R52") (pin "2") (pinfunction "2_2") (pintype "passive"))
    )
    (net (code "76") (name "Net-(IC9D-OUT)") (class "Default")
      (node (ref "IC9") (pin "14") (pinfunction "OUT_14") (pintype "output"))
      (node (ref "R52") (pin "1") (pinfunction "1_1") (pintype "passive"))
      (node (ref "R86") (pin "2") (pinfunction "2_2") (pintype "passive"))
    )
    (net (code "77") (name "Net-(IC10A-+IN)") (class "Default")
      (node (ref "C34") (pin "2") (pinfunction "2_2") (pintype "passive"))
      (node (ref "IC10") (pin "3") (pinfunction "+IN_3") (pintype "input"))
      (node (ref "IC7") (pin "1") (pinfunction "OUT_1") (pintype "output"))
      (node (ref "R45") (pin "2") (pinfunction "2_2") (pintype "passive"))
    )
    (net (code "78") (name "Net-(IC10A--IN)") (class "Default")
      (node (ref "IC10") (pin "2") (pinfunction "-IN_2") (pintype "input"))
      (node (ref "LED10") (pin "2") (pinfunction "2_2") (pintype "bidirectional"))
      (node (ref "R79") (pin "1") (pinfunction "1_1") (pintype "passive"))
    )
    (net (code "79") (name "Net-(IC10A-OUT)") (class "Default")
      (node (ref "IC10") (pin "1") (pinfunction "OUT_1") (pintype "output"))
      (node (ref "LED10") (pin "1") (pinfunction "1_1") (pintype "bidirectional"))
    )
    (net (code "80") (name "Net-(IC10B-+IN)") (class "Default")
      (node (ref "C43") (pin "2") (pinfunction "2_2") (pintype "passive"))
      (node (ref "IC10") (pin "5") (pinfunction "+IN_5") (pintype "input"))
      (node (ref "IC7") (pin "7") (pinfunction "OUT_7") (pintype "output"))
      (node (ref "R62") (pin "2") (pinfunction "2_2") (pintype "passive"))
    )
    (net (code "81") (name "Net-(IC10B--IN)") (class "Default")
      (node (ref "IC10") (pin "6") (pinfunction "-IN_6") (pintype "input"))
      (node (ref "LED9") (pin "2") (pinfunction "2_2") (pintype "bidirectional"))
      (node (ref "R78") (pin "1") (pinfunction "1_1") (pintype "passive"))
    )
    (net (code "82") (name "Net-(IC10B-OUT)") (class "Default")
      (node (ref "IC10") (pin "7") (pinfunction "OUT_7") (pintype "output"))
      (node (ref "LED9") (pin "1") (pinfunction "1_1") (pintype "bidirectional"))
    )
    (net (code "83") (name "Net-(IC10C-+IN)") (class "Default")
      (node (ref "C44") (pin "2") (pinfunction "2_2") (pintype "passive"))
      (node (ref "IC10") (pin "10") (pinfunction "+IN_10") (pintype "input"))
      (node (ref "IC7") (pin "8") (pinfunction "OUT_8") (pintype "output"))
      (node (ref "R63") (pin "2") (pinfunction "2_2") (pintype "passive"))
    )
    (net (code "84") (name "Net-(IC10C--IN)") (class "Default")
      (node (ref "IC10") (pin "9") (pinfunction "-IN_9") (pintype "input"))
      (node (ref "LED12") (pin "2") (pinfunction "2_2") (pintype "bidirectional"))
      (node (ref "R81") (pin "1") (pinfunction "1_1") (pintype "passive"))
    )
    (net (code "85") (name "Net-(IC10C-OUT)") (class "Default")
      (node (ref "IC10") (pin "8") (pinfunction "OUT_8") (pintype "output"))
      (node (ref "LED12") (pin "1") (pinfunction "1_1") (pintype "bidirectional"))
    )
    (net (code "86") (name "Net-(IC10D-+IN)") (class "Default")
      (node (ref "C35") (pin "2") (pinfunction "2_2") (pintype "passive"))
      (node (ref "IC10") (pin "12") (pinfunction "+IN_12") (pintype "input"))
      (node (ref "IC7") (pin "14") (pinfunction "OUT_14") (pintype "output"))
      (node (ref "R46") (pin "2") (pinfunction "2_2") (pintype "passive"))
    )
    (net (code "87") (name "Net-(IC10D--IN)") (class "Default")
      (node (ref "IC10") (pin "13") (pinfunction "-IN_13") (pintype "input"))
      (node (ref "LED11") (pin "2") (pinfunction "2_2") (pintype "bidirectional"))
      (node (ref "R80") (pin "1") (pinfunction "1_1") (pintype "passive"))
    )
    (net (code "88") (name "Net-(IC10D-OUT)") (class "Default")
      (node (ref "IC10") (pin "14") (pinfunction "OUT_14") (pintype "output"))
      (node (ref "LED11") (pin "1") (pinfunction "1_1") (pintype "bidirectional"))
    )
    (net (code "89") (name "Net-(J1-3)") (class "Default")
      (node (ref "C53") (pin "1") (pinfunction "1_1") (pintype "passive"))
      (node (ref "J1") (pin "P3") (pinfunction "3_P3") (pintype "passive"))
      (node (ref "R64") (pin "2") (pinfunction "2_2") (pintype "passive"))
    )
    (net (code "90") (name "Net-(J2-3)") (class "Default")
      (node (ref "C45") (pin "1") (pinfunction "1_1") (pintype "passive"))
      (node (ref "J2") (pin "P3") (pinfunction "3_P3") (pintype "passive"))
      (node (ref "R33") (pin "2") (pinfunction "2_2") (pintype "passive"))
    )
    (net (code "91") (name "Net-(J3-2)") (class "Default")
      (node (ref "J3") (pin "P2") (pinfunction "2_P2") (pintype "passive"))
      (node (ref "R76") (pin "2") (pinfunction "2_2") (pintype "passive"))
    )
    (net (code "92") (name "Net-(J3-3)") (class "Default")
      (node (ref "J3") (pin "P3") (pinfunction "3_P3") (pintype "passive"))
      (node (ref "R26") (pin "1") (pinfunction "1_1") (pintype "passive"))
    )
    (net (code "93") (name "Net-(J4-3)") (class "Default")
      (node (ref "C56") (pin "1") (pinfunction "1_1") (pintype "passive"))
      (node (ref "J4") (pin "P3") (pinfunction "3_P3") (pintype "passive"))
      (node (ref "R65") (pin "2") (pinfunction "2_2") (pintype "passive"))
    )
    (net (code "94") (name "Net-(J5-3)") (class "Default")
      (node (ref "C58") (pin "1") (pinfunction "1_1") (pintype "passive"))
      (node (ref "J5") (pin "P3") (pinfunction "3_P3") (pintype "passive"))
      (node (ref "R66") (pin "2") (pinfunction "2_2") (pintype "passive"))
    )
    (net (code "95") (name "Net-(J6-3)") (class "Default")
      (node (ref "C54") (pin "1") (pinfunction "1_1") (pintype "passive"))
      (node (ref "J6") (pin "P3") (pinfunction "3_P3") (pintype "passive"))
      (node (ref "R32") (pin "2") (pinfunction "2_2") (pintype "passive"))
    )
    (net (code "96") (name "Net-(J7-3)") (class "Default")
      (node (ref "C55") (pin "1") (pinfunction "1_1") (pintype "passive"))
      (node (ref "J7") (pin "P3") (pinfunction "3_P3") (pintype "passive"))
      (node (ref "R35") (pin "2") (pinfunction "2_2") (pintype "passive"))
    )
    (net (code "97") (name "Net-(J8-3)") (class "Default")
      (node (ref "C57") (pin "1") (pinfunction "1_1") (pintype "passive"))
      (node (ref "J8") (pin "P3") (pinfunction "3_P3") (pintype "passive"))
      (node (ref "R34") (pin "2") (pinfunction "2_2") (pintype "passive"))
    )
    (net (code "98") (name "Net-(J9-2)") (class "Default")
      (node (ref "J9") (pin "P2") (pinfunction "2_P2") (pintype "passive"))
      (node (ref "R77") (pin "2") (pinfunction "2_2") (pintype "passive"))
    )
    (net (code "99") (name "Net-(J9-3)") (class "Default")
      (node (ref "J9") (pin "P3") (pinfunction "3_P3") (pintype "passive"))
      (node (ref "R27") (pin "1") (pinfunction "1_1") (pintype "passive"))
    )
    (net (code "100") (name "Net-(J10-3)") (class "Default")
      (node (ref "J10") (pin "P3") (pinfunction "3_P3") (pintype "passive"))
      (node (ref "R85") (pin "1") (pinfunction "1_1") (pintype "passive"))
    )
    (net (code "101") (name "Net-(J11-3)") (class "Default")
      (node (ref "J11") (pin "P3") (pinfunction "3_P3") (pintype "passive"))
      (node (ref "R86") (pin "1") (pinfunction "1_1") (pintype "passive"))
    )
    (net (code "102") (name "Net-(J12-3)") (class "Default")
      (node (ref "J12") (pin "P3") (pinfunction "3_P3") (pintype "passive"))
      (node (ref "R87") (pin "1") (pinfunction "1_1") (pintype "passive"))
    )
    (net (code "103") (name "Net-(J13-3)") (class "Default")
      (node (ref "J13") (pin "P3") (pinfunction "3_P3") (pintype "passive"))
      (node (ref "R60") (pin "1") (pinfunction "1_1") (pintype "passive"))
      (node (ref "R62") (pin "1") (pinfunction "1_1") (pintype "passive"))
    )
    (net (code "104") (name "Net-(J14-3)") (class "Default")
      (node (ref "J14") (pin "P3") (pinfunction "3_P3") (pintype "passive"))
      (node (ref "R43") (pin "1") (pinfunction "1_1") (pintype "passive"))
      (node (ref "R45") (pin "1") (pinfunction "1_1") (pintype "passive"))
    )
    (net (code "105") (name "Net-(J15-3)") (class "Default")
      (node (ref "J15") (pin "P3") (pinfunction "3_P3") (pintype "passive"))
      (node (ref "R44") (pin "1") (pinfunction "1_1") (pintype "passive"))
      (node (ref "R46") (pin "1") (pinfunction "1_1") (pintype "passive"))
    )
    (net (code "106") (name "Net-(J16-3)") (class "Default")
      (node (ref "J16") (pin "P3") (pinfunction "3_P3") (pintype "passive"))
      (node (ref "R61") (pin "1") (pinfunction "1_1") (pintype "passive"))
      (node (ref "R63") (pin "1") (pinfunction "1_1") (pintype "passive"))
    )
    (net (code "107") (name "Net-(JP2-Pad1)") (class "Default")
      (node (ref "JP2") (pin "1") (pinfunction "1_1") (pintype "passive"))
      (node (ref "R3") (pin "1") (pinfunction "1_1") (pintype "passive"))
    )
    (net (code "108") (name "Net-(JP2-Pad2)") (class "Default")
      (node (ref "JP2") (pin "2") (pinfunction "2_2") (pintype "passive"))
      (node (ref "R2") (pin "1") (pinfunction "1_1") (pintype "passive"))
    )
    (net (code "109") (name "Net-(LED1-GRN)") (class "Default")
      (node (ref "LED1") (pin "1") (pinfunction "GRN_1") (pintype "bidirectional"))
      (node (ref "R10") (pin "2") (pinfunction "2_2") (pintype "passive"))
    )
    (net (code "110") (name "Net-(LED1-RED)") (class "Default")
      (node (ref "LED1") (pin "3") (pinfunction "RED_3") (pintype "bidirectional"))
      (node (ref "R9") (pin "2") (pinfunction "2_2") (pintype "passive"))
    )
    (net (code "111") (name "Net-(LED2-GRN)") (class "Default")
      (node (ref "LED2") (pin "1") (pinfunction "GRN_1") (pintype "bidirectional"))
      (node (ref "R12") (pin "2") (pinfunction "2_2") (pintype "passive"))
    )
    (net (code "112") (name "Net-(LED2-RED)") (class "Default")
      (node (ref "LED2") (pin "3") (pinfunction "RED_3") (pintype "bidirectional"))
      (node (ref "R11") (pin "2") (pinfunction "2_2") (pintype "passive"))
    )
    (net (code "113") (name "Net-(LED3-GRN)") (class "Default")
      (node (ref "LED3") (pin "1") (pinfunction "GRN_1") (pintype "bidirectional"))
      (node (ref "R18") (pin "2") (pinfunction "2_2") (pintype "passive"))
    )
    (net (code "114") (name "Net-(LED3-RED)") (class "Default")
      (node (ref "LED3") (pin "3") (pinfunction "RED_3") (pintype "bidirectional"))
      (node (ref "R19") (pin "2") (pinfunction "2_2") (pintype "passive"))
    )
    (net (code "115") (name "Net-(LED4-GRN)") (class "Default")
      (node (ref "LED4") (pin "1") (pinfunction "GRN_1") (pintype "bidirectional"))
      (node (ref "R17") (pin "2") (pinfunction "2_2") (pintype "passive"))
    )
    (net (code "116") (name "Net-(LED4-RED)") (class "Default")
      (node (ref "LED4") (pin "3") (pinfunction "RED_3") (pintype "bidirectional"))
      (node (ref "R15") (pin "2") (pinfunction "2_2") (pintype "passive"))
    )
    (net (code "117") (name "Net-(LED5-GRN)") (class "Default")
      (node (ref "LED5") (pin "1") (pinfunction "GRN_1") (pintype "bidirectional"))
      (node (ref "R36") (pin "2") (pinfunction "2_2") (pintype "passive"))
    )
    (net (code "118") (name "Net-(LED6-Pad2)") (class "Default")
      (node (ref "LED6") (pin "2") (pinfunction "2_2") (pintype "bidirectional"))
      (node (ref "R82") (pin "2") (pinfunction "2_2") (pintype "passive"))
    )
    (net (code "119") (name "Net-(LED7-Pad2)") (class "Default")
      (node (ref "LED7") (pin "2") (pinfunction "2_2") (pintype "bidirectional"))
      (node (ref "R83") (pin "2") (pinfunction "2_2") (pintype "passive"))
    )
    (net (code "120") (name "Net-(LED8-Pad2)") (class "Default")
      (node (ref "LED8") (pin "2") (pinfunction "2_2") (pintype "bidirectional"))
      (node (ref "R84") (pin "2") (pinfunction "2_2") (pintype "passive"))
    )
    (net (code "121") (name "Net-(Q1B-2)") (class "Default")
      (node (ref "C4") (pin "2") (pinfunction "2_2") (pintype "passive"))
      (node (ref "Q1") (pin "3") (pinfunction "2_3") (pintype "passive"))
      (node (ref "R8") (pin "2") (pinfunction "2_2") (pintype "passive"))
    )
    (net (code "122") (name "Net-(R1-Pad2)") (class "Default")
      (node (ref "R1") (pin "2") (pinfunction "2_2") (pintype "passive"))
      (node (ref "SW1") (pin "L1") (pinfunction "L1_L1") (pintype "passive"))
    )
    (net (code "123") (name "Net-(R5-Pad2)") (class "Default")
      (node (ref "R5") (pin "2") (pinfunction "2_2") (pintype "passive"))
      (node (ref "SW2") (pin "L1") (pinfunction "L1_L1") (pintype "passive"))
    )
    (net (code "124") (name "RESET") (class "Default")
      (node (ref "C7") (pin "1") (pinfunction "1_1") (pintype "passive"))
      (node (ref "IC2") (pin "7") (pinfunction "NRST_7") (pintype "bidirectional"))
      (node (ref "JP1") (pin "4") (pinfunction "4_4") (pintype "passive"))
      (node (ref "R6") (pin "1") (pinfunction "1_1") (pintype "passive"))
    )
    (net (code "125") (name "RX") (class "Default")
      (node (ref "IC2") (pin "43") (pinfunction "PA10/USART1_RX/TIM1_CH3_43") (pintype "bidirectional"))
      (node (ref "R3") (pin "2") (pinfunction "2_2") (pintype "passive"))
    )
    (net (code "126") (name "SWCLK") (class "Default")
      (node (ref "IC2") (pin "49") (pinfunction "PA14/JTCK-SWCLK_49") (pintype "bidirectional"))
      (node (ref "JP1") (pin "3") (pinfunction "3_3") (pintype "passive"))
    )
    (net (code "127") (name "SWDIO") (class "Default")
      (node (ref "IC2") (pin "46") (pinfunction "PA13/JTMS-SWDAT_46") (pintype "bidirectional"))
      (node (ref "JP1") (pin "2") (pinfunction "2_2") (pintype "passive"))
    )
    (net (code "128") (name "SW_T_DV") (class "Default")
      (node (ref "IC2") (pin "30") (pinfunction "PB11/I2C2_SDA/USART3_RX_30") (pintype "bidirectional"))
      (node (ref "SW1") (pin "P2") (pinfunction "A2_P2") (pintype "passive"))
      (node (ref "SW1") (pin "P5") (pinfunction "B2_P5") (pintype "passive"))
    )
    (net (code "129") (name "SW_T_MODE") (class "Default")
      (node (ref "IC2") (pin "35") (pinfunction "PB14/SPI2_MISO/USART3_RTS/TIM1_CH2N_35") (pintype "bidirectional"))
      (node (ref "SW3") (pin "3") (pinfunction "3_3") (pintype "passive"))
      (node (ref "SW3") (pin "4") (pinfunction "4_4") (pintype "passive"))
    )
    (net (code "130") (name "SW_T_RANGE") (class "Default")
      (node (ref "IC2") (pin "36") (pinfunction "PB15/SPI2_MOSI/I2S2_SD/TIM1_CH3N_36") (pintype "bidirectional"))
      (node (ref "SW5") (pin "3") (pinfunction "3_3") (pintype "passive"))
      (node (ref "SW5") (pin "4") (pinfunction "4_4") (pintype "passive"))
    )
    (net (code "131") (name "SW_X_DV") (class "Default")
      (node (ref "IC2") (pin "4") (pinfunction "PC15/OSC_OUT_4") (pintype "bidirectional"))
      (node (ref "SW2") (pin "P2") (pinfunction "A2_P2") (pintype "passive"))
      (node (ref "SW2") (pin "P5") (pinfunction "B2_P5") (pintype "passive"))
    )
    (net (code "132") (name "SW_X_EXT") (class "Default")
      (node (ref "IC2") (pin "54") (pinfunction "PD2/TIM3-ETR_54") (pintype "bidirectional"))
      (node (ref "SW7") (pin "3") (pinfunction "3_3") (pintype "passive"))
      (node (ref "SW7") (pin "4") (pinfunction "4_4") (pintype "passive"))
    )
    (net (code "133") (name "SW_X_MODE") (class "Default")
      (node (ref "IC2") (pin "2") (pinfunction "PC13-TAMPER-RTC_2") (pintype "bidirectional"))
      (node (ref "SW4") (pin "3") (pinfunction "3_3") (pintype "passive"))
      (node (ref "SW4") (pin "4") (pinfunction "4_4") (pintype "passive"))
    )
    (net (code "134") (name "SW_X_RANGE") (class "Default")
      (node (ref "IC2") (pin "58") (pinfunction "PB6/I2C1_SCL/TIM4_CH1/USART1_TX_58") (pintype "bidirectional"))
      (node (ref "SW6") (pin "3") (pinfunction "3_3") (pintype "passive"))
      (node (ref "SW6") (pin "4") (pinfunction "4_4") (pintype "passive"))
    )
    (net (code "135") (name "TX") (class "Default")
      (node (ref "IC2") (pin "42") (pinfunction "PA9/USART1_TX/TIM1_CH2_42") (pintype "bidirectional"))
      (node (ref "R2") (pin "2") (pinfunction "2_2") (pintype "passive"))
    )
    (net (code "136") (name "T_CLOCK") (class "Default")
      (node (ref "IC2") (pin "40") (pinfunction "PC9/I2S2_CKIN/I2S3_CKIN_40") (pintype "bidirectional"))
      (node (ref "Q2") (pin "C") (pinfunction "C_C") (pintype "passive"))
      (node (ref "R22") (pin "1") (pinfunction "1_1") (pintype "passive"))
    )
    (net (code "137") (name "VCC") (class "Default")
      (node (ref "C11") (pin "+") (pinfunction "+_+") (pintype "passive"))
      (node (ref "C39") (pin "1") (pinfunction "1_1") (pintype "passive"))
      (node (ref "C48") (pin "1") (pinfunction "1_1") (pintype "passive"))
      (node (ref "C50") (pin "1") (pinfunction "1_1") (pintype "passive"))
      (node (ref "IC10") (pin "4") (pinfunction "V+_4") (pintype "power_in"))
      (node (ref "IC7") (pin "4") (pinfunction "V+_4") (pintype "power_in"))
      (node (ref "IC9") (pin "4") (pinfunction "V+_4") (pintype "power_in"))
      (node (ref "L2") (pin "1") (pinfunction "1_1") (pintype "passive"))
    )
    (net (code "138") (name "VEE") (class "Default")
      (node (ref "C22") (pin "-") (pinfunction "-_-") (pintype "passive"))
      (node (ref "C37") (pin "2") (pinfunction "2_2") (pintype "passive"))
      (node (ref "C49") (pin "2") (pinfunction "2_2") (pintype "passive"))
      (node (ref "IC10") (pin "11") (pinfunction "V-_11") (pintype "power_in"))
      (node (ref "IC7") (pin "11") (pinfunction "V-_11") (pintype "power_in"))
      (node (ref "L4") (pin "1") (pinfunction "1_1") (pintype "passive"))
      (node (ref "R68") (pin "1") (pinfunction "1_1") (pintype "passive"))
    )
    (net (code "139") (name "VREF") (class "Default")
      (node (ref "C25") (pin "1") (pinfunction "1_1") (pintype "passive"))
      (node (ref "IC4") (pin "3") (pinfunction "VREFH_3") (pintype "bidirectional"))
      (node (ref "R74") (pin "2") (pinfunction "2_2") (pintype "passive"))
    )
    (net (code "140") (name "VREF_BIAS") (class "Default")
      (node (ref "C51") (pin "1") (pinfunction "1_1") (pintype "passive"))
      (node (ref "IC7") (pin "10") (pinfunction "+IN_10") (pintype "input"))
      (node (ref "IC7") (pin "12") (pinfunction "+IN_12") (pintype "input"))
      (node (ref "IC7") (pin "3") (pinfunction "+IN_3") (pintype "input"))
      (node (ref "IC7") (pin "5") (pinfunction "+IN_5") (pintype "input"))
      (node (ref "R73") (pin "2") (pinfunction "2_2") (pintype "passive"))
      (node (ref "R74") (pin "1") (pinfunction "1_1") (pintype "passive"))
    )
    (net (code "141") (name "X_CLOCK") (class "Default")
      (node (ref "IC2") (pin "41") (pinfunction "PA8/USART1_CK/TIM1_CH1/MCO_41") (pintype "bidirectional"))
      (node (ref "Q3") (pin "C") (pinfunction "C_C") (pintype "passive"))
      (node (ref "R23") (pin "1") (pinfunction "1_1") (pintype "passive"))
    )
    (net (code "142") (name "unconnected-(IC2-PC14{slash}OSC32_IN-Pad3)") (class "Default")
      (node (ref "IC2") (pin "3") (pinfunction "PC14/OSC32_IN_3") (pintype "bidirectional"))
    )
    (net (code "143") (name "unconnected-(J10-2-PadP2)") (class "Default")
      (node (ref "J10") (pin "P2") (pinfunction "2_P2") (pintype "passive"))
    )
    (net (code "144") (name "unconnected-(J11-2-PadP2)") (class "Default")
      (node (ref "J11") (pin "P2") (pinfunction "2_P2") (pintype "passive"))
    )
    (net (code "145") (name "unconnected-(J12-2-PadP2)") (class "Default")
      (node (ref "J12") (pin "P2") (pinfunction "2_P2") (pintype "passive"))
    )
    (net (code "146") (name "unconnected-(J13-2-PadP2)") (class "Default")
      (node (ref "J13") (pin "P2") (pinfunction "2_P2") (pintype "passive"))
    )
    (net (code "147") (name "unconnected-(J14-2-PadP2)") (class "Default")
      (node (ref "J14") (pin "P2") (pinfunction "2_P2") (pintype "passive"))
    )
    (net (code "148") (name "unconnected-(J15-2-PadP2)") (class "Default")
      (node (ref "J15") (pin "P2") (pinfunction "2_P2") (pintype "passive"))
    )
    (net (code "149") (name "unconnected-(J16-2-PadP2)") (class "Default")
      (node (ref "J16") (pin "P2") (pinfunction "2_P2") (pintype "passive"))
    )
    (net (code "150") (name "unconnected-(LED5-RED-Pad3)") (class "Default")
      (node (ref "LED5") (pin "3") (pinfunction "RED_3") (pintype "bidirectional"))
    )
    (net (code "151") (name "unconnected-(SW1A-A1-PadP1)") (class "Default")
      (node (ref "SW1") (pin "P1") (pinfunction "A1_P1") (pintype "passive"))
    )
    (net (code "152") (name "unconnected-(SW1A-B1-PadP4)") (class "Default")
      (node (ref "SW1") (pin "P4") (pinfunction "B1_P4") (pintype "passive"))
    )
    (net (code "153") (name "unconnected-(SW2A-A1-PadP1)") (class "Default")
      (node (ref "SW2") (pin "P1") (pinfunction "A1_P1") (pintype "passive"))
    )
    (net (code "154") (name "unconnected-(SW2A-B1-PadP4)") (class "Default")
      (node (ref "SW2") (pin "P4") (pinfunction "B1_P4") (pintype "passive"))
    )
  )
)
